# SCH_Amiga-KickSmash-32-in-system-flash_2.net
KiCad netlist of a schematic drawn in EasyEDA
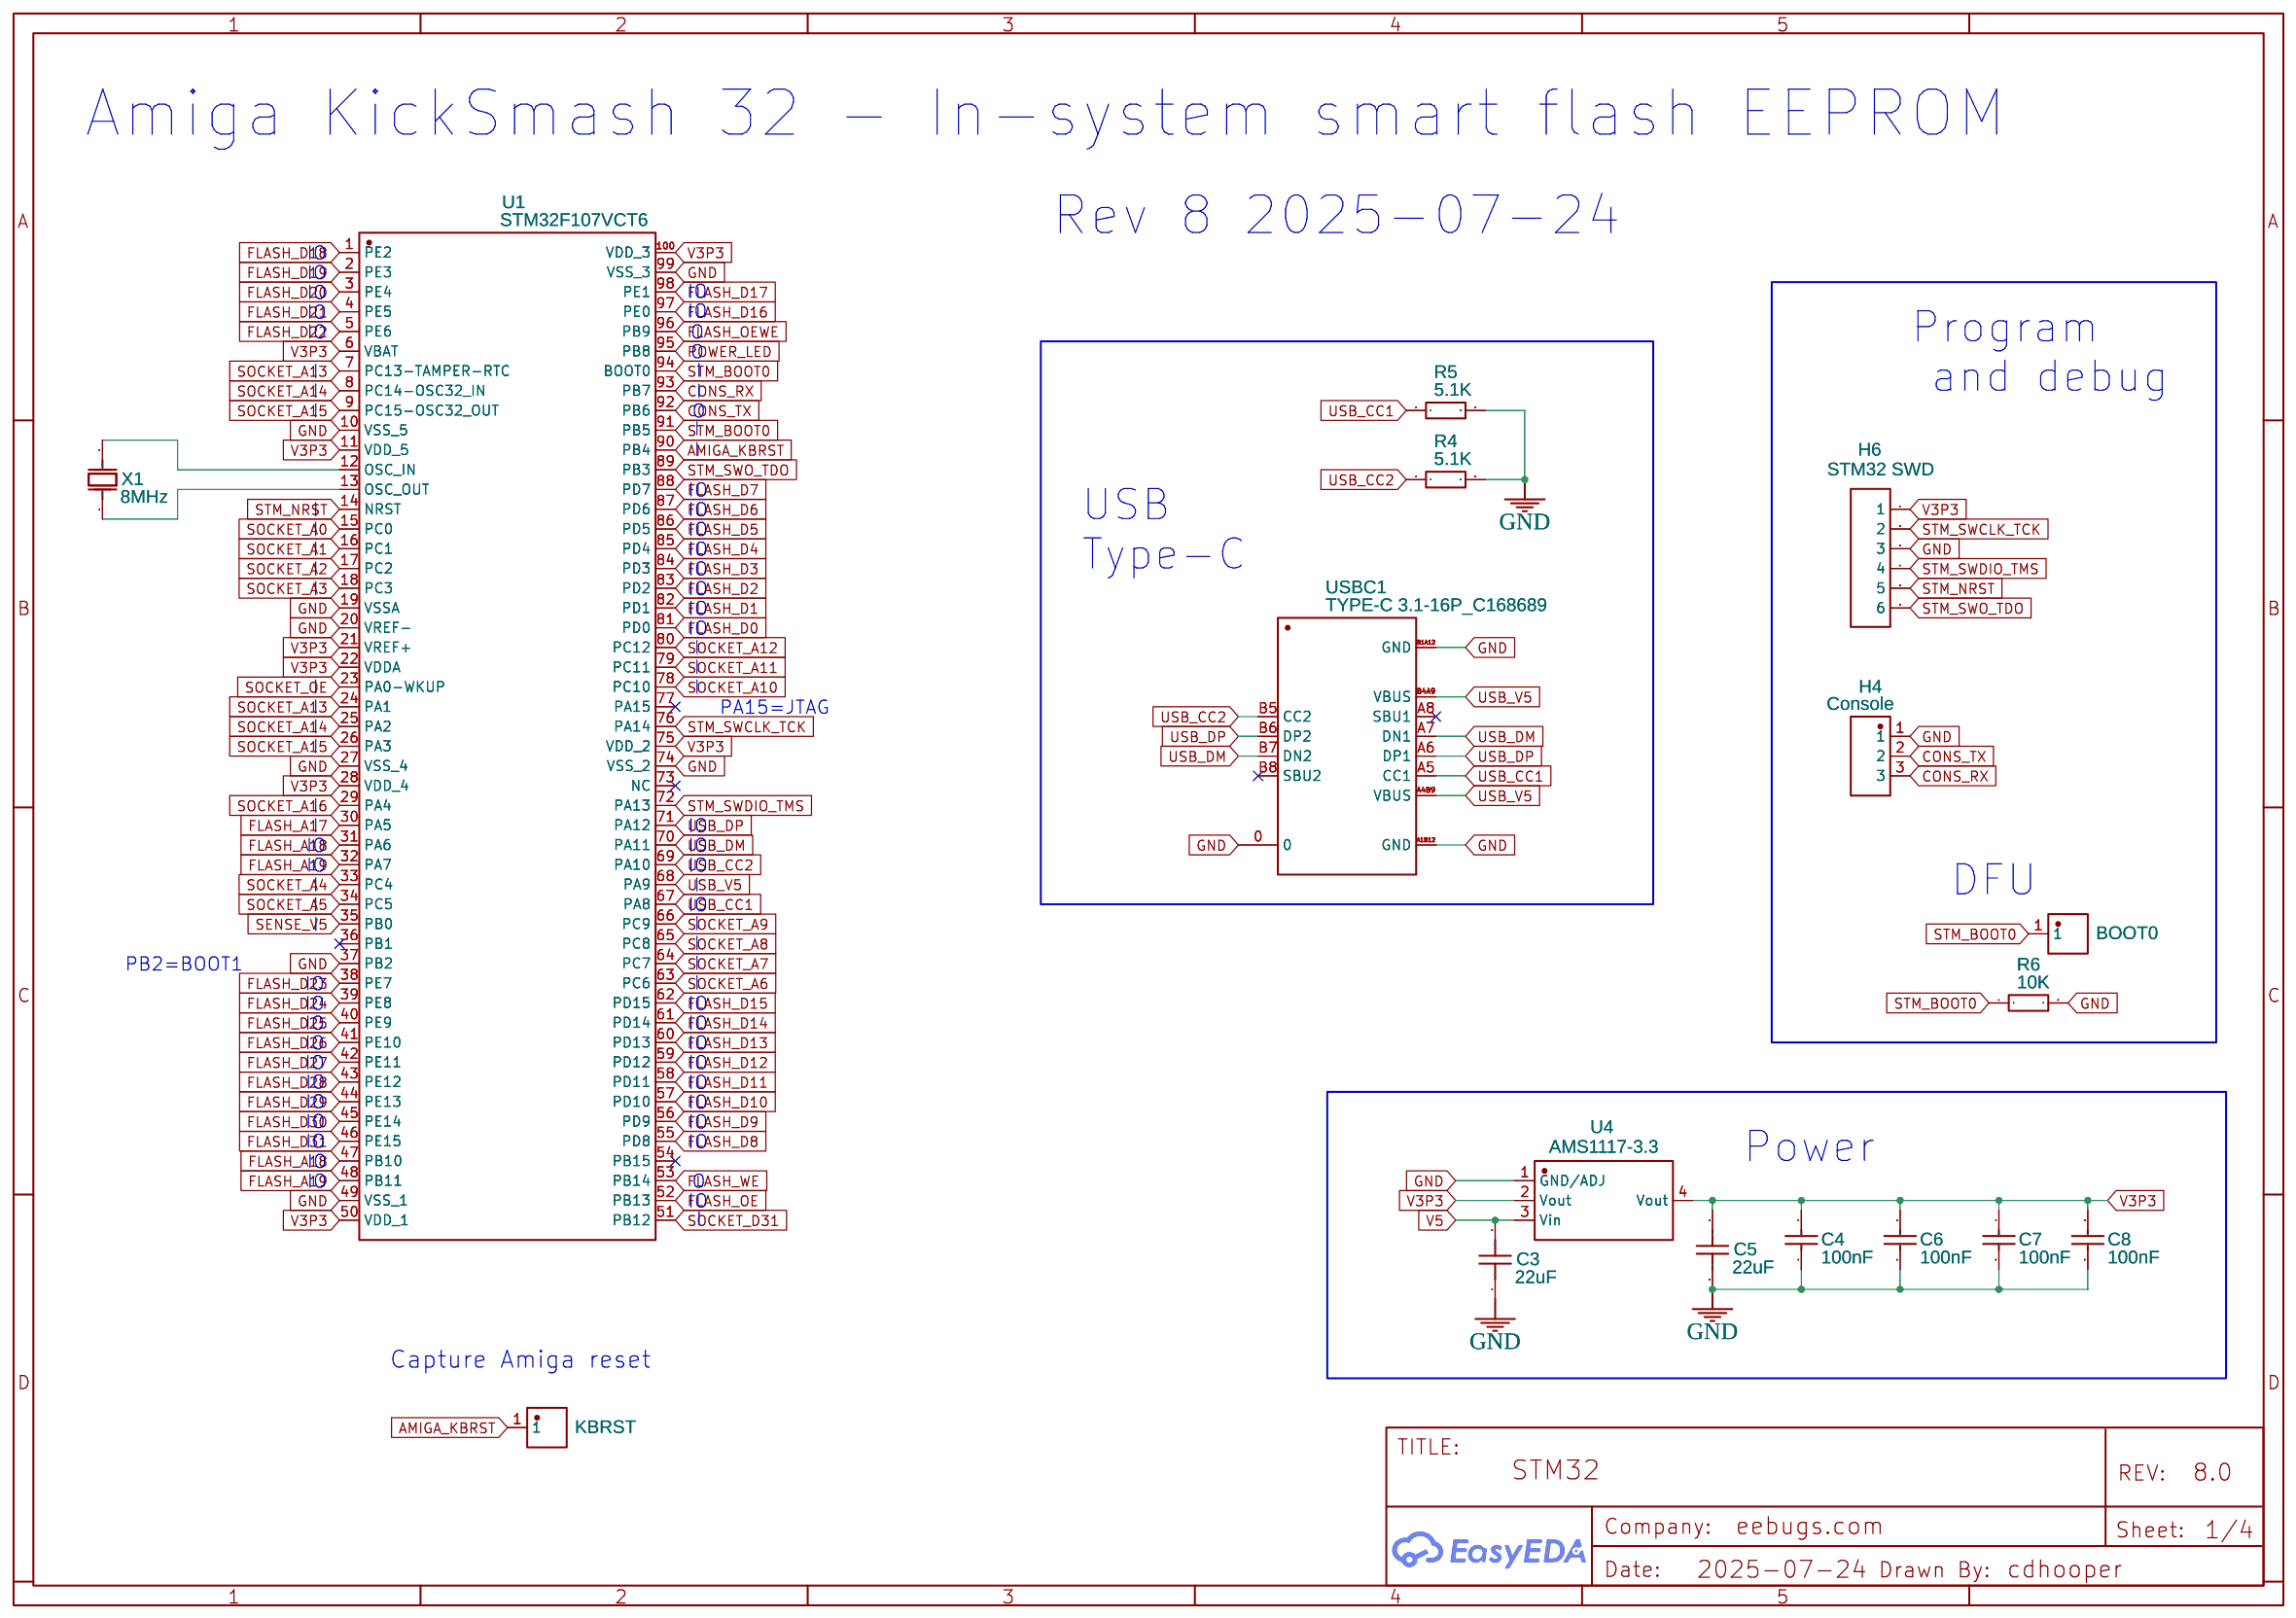
[diagram p0: STM32]
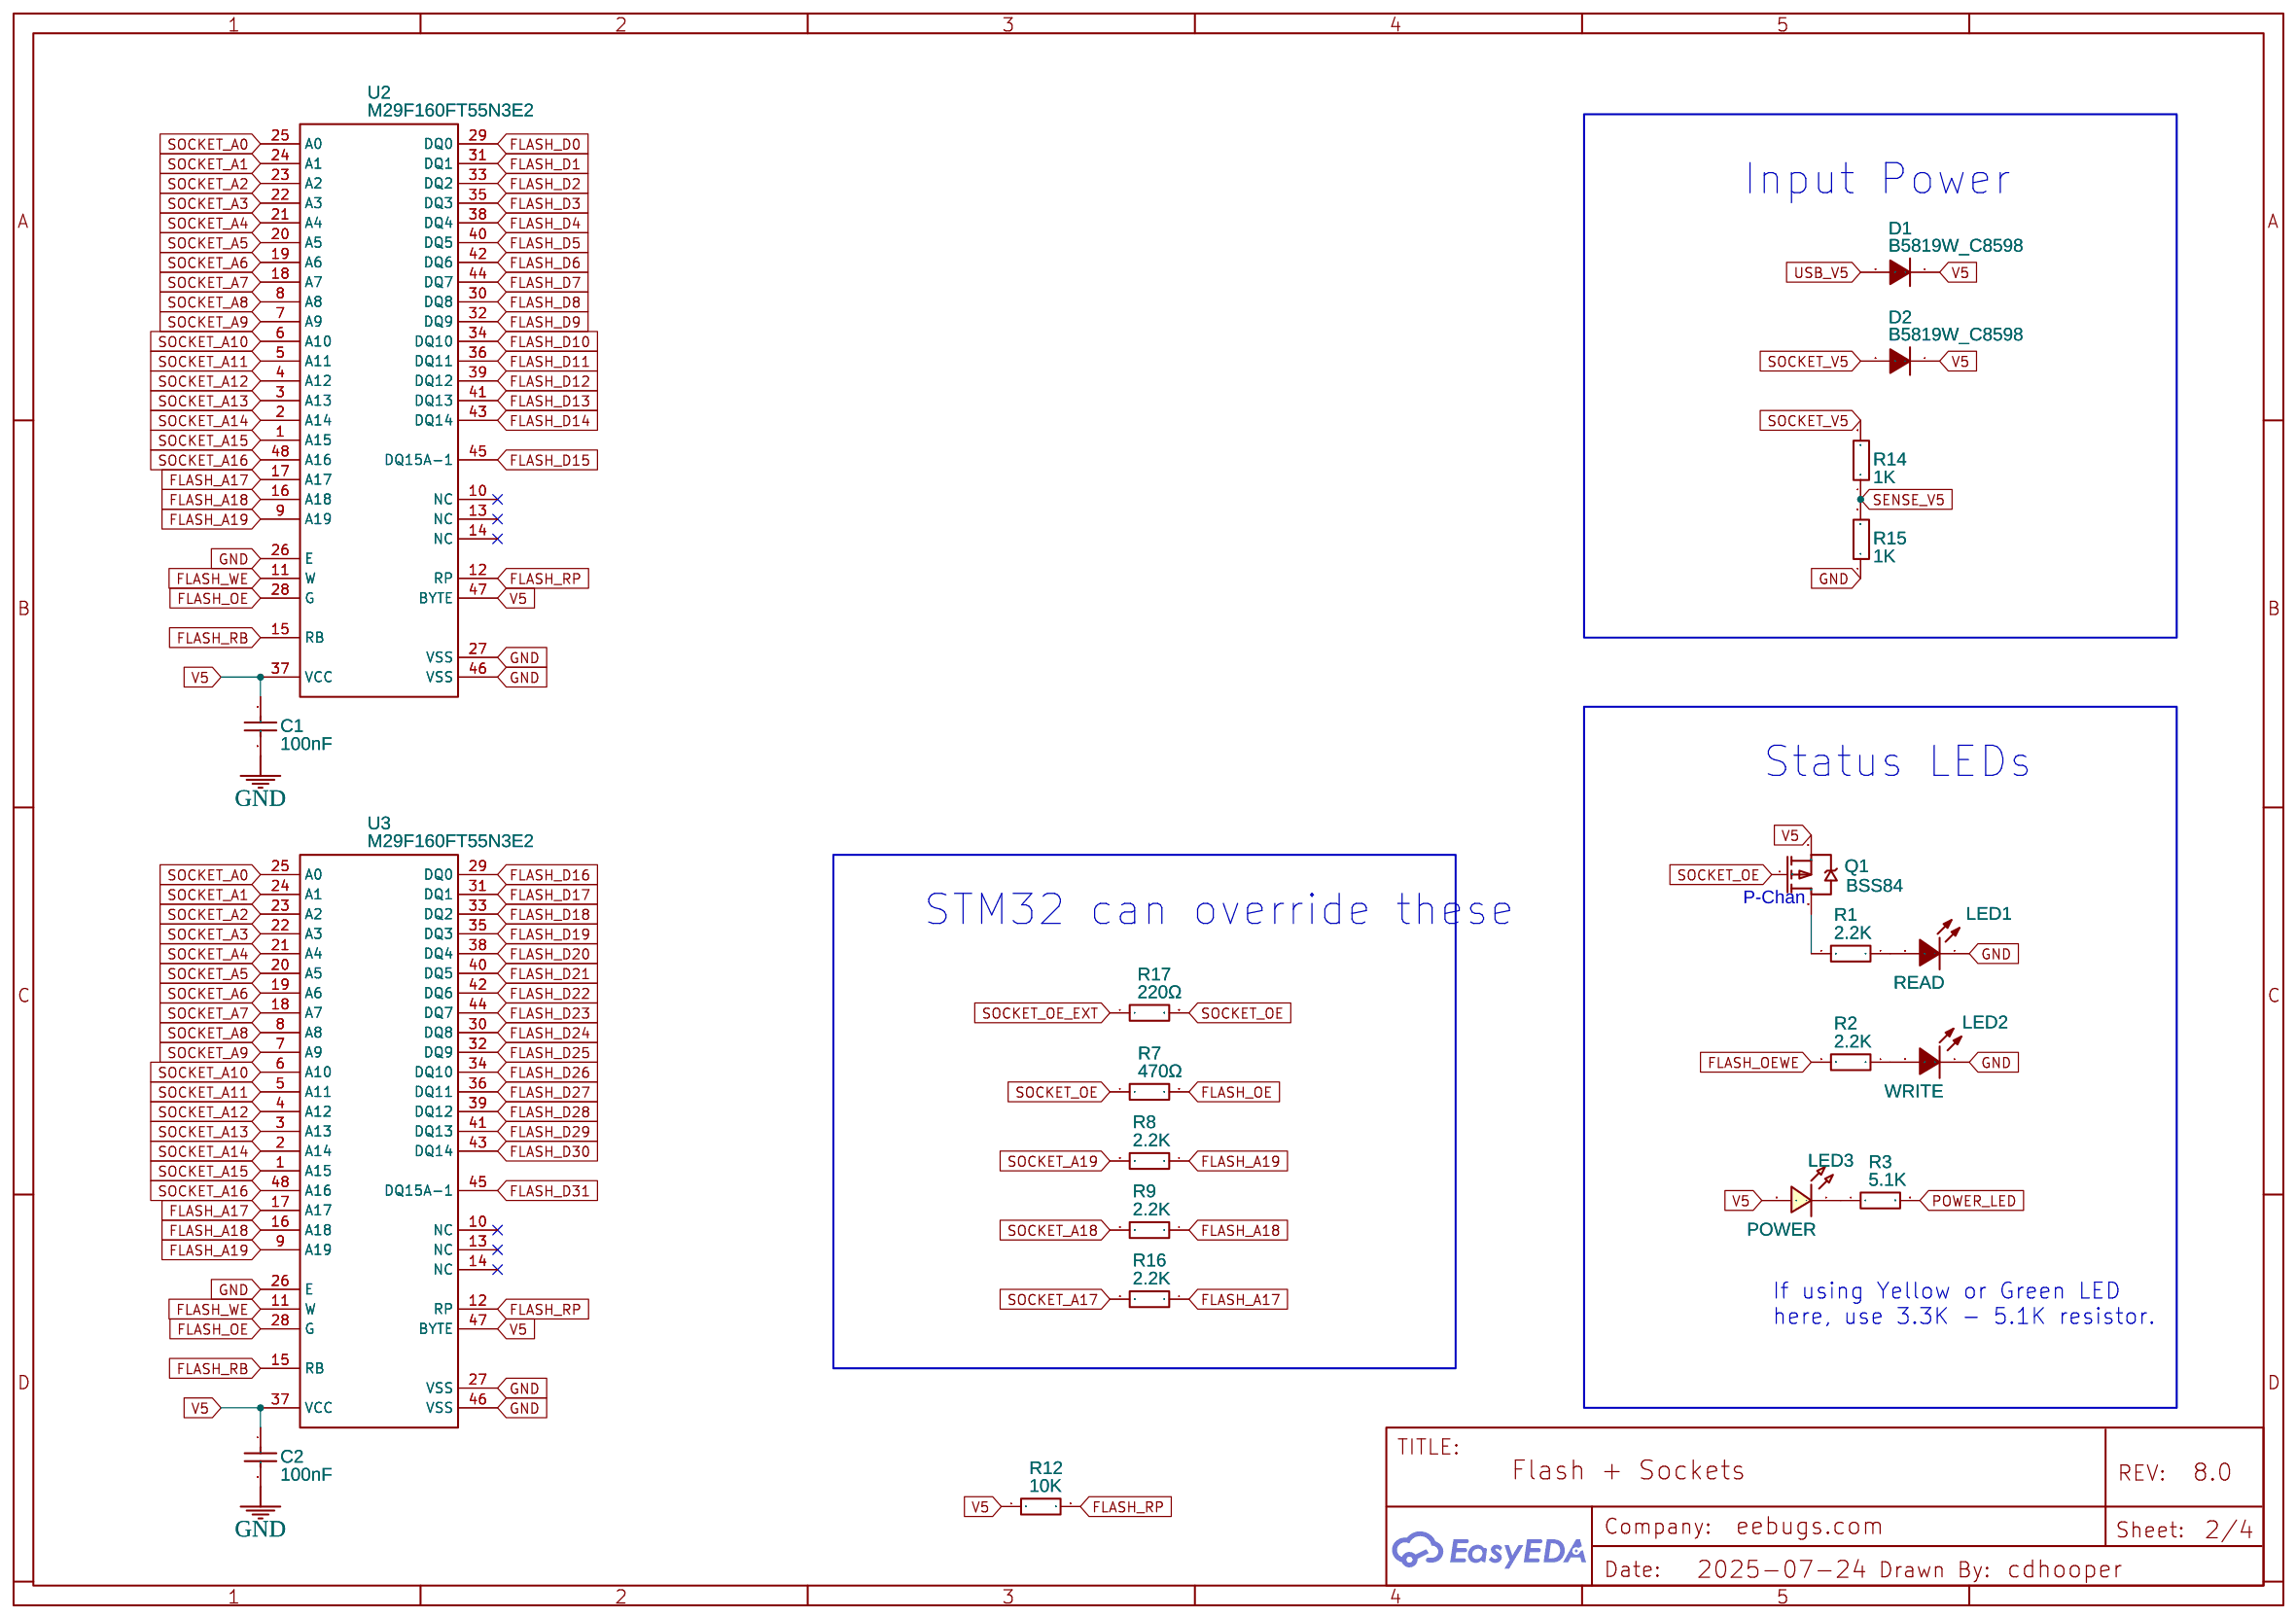
[diagram p1: Flash]
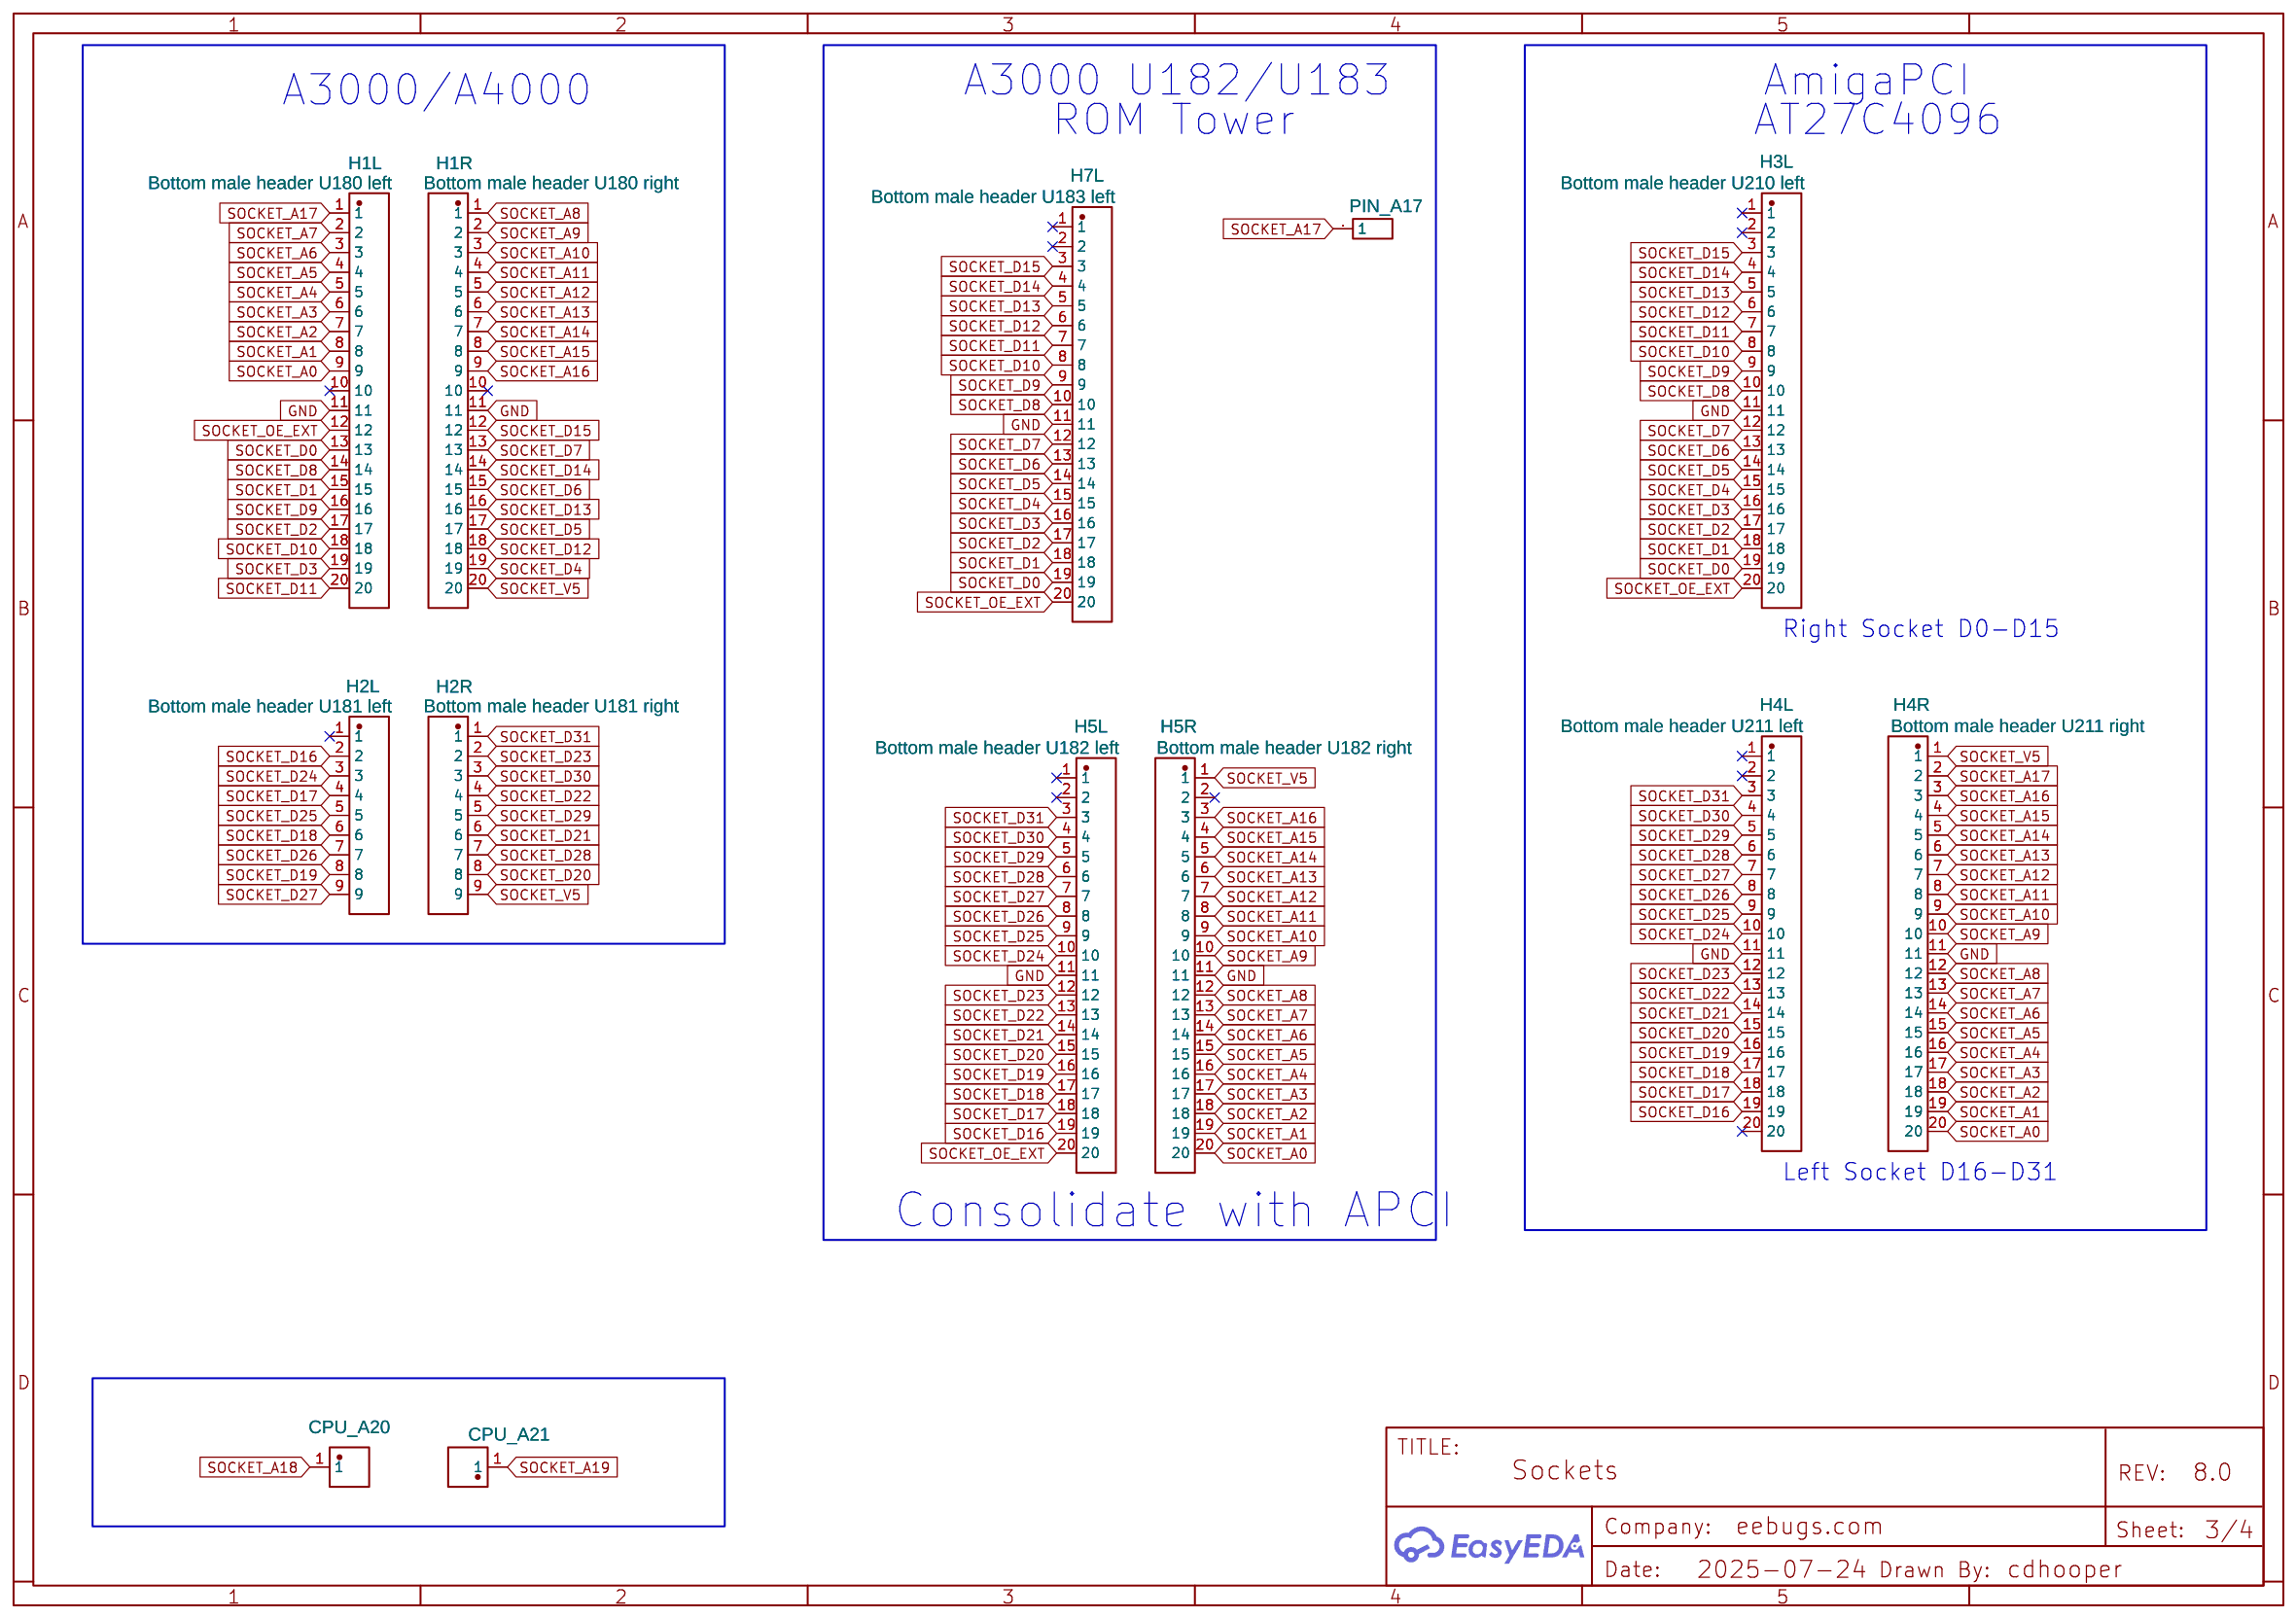
[diagram p2: Sockets]
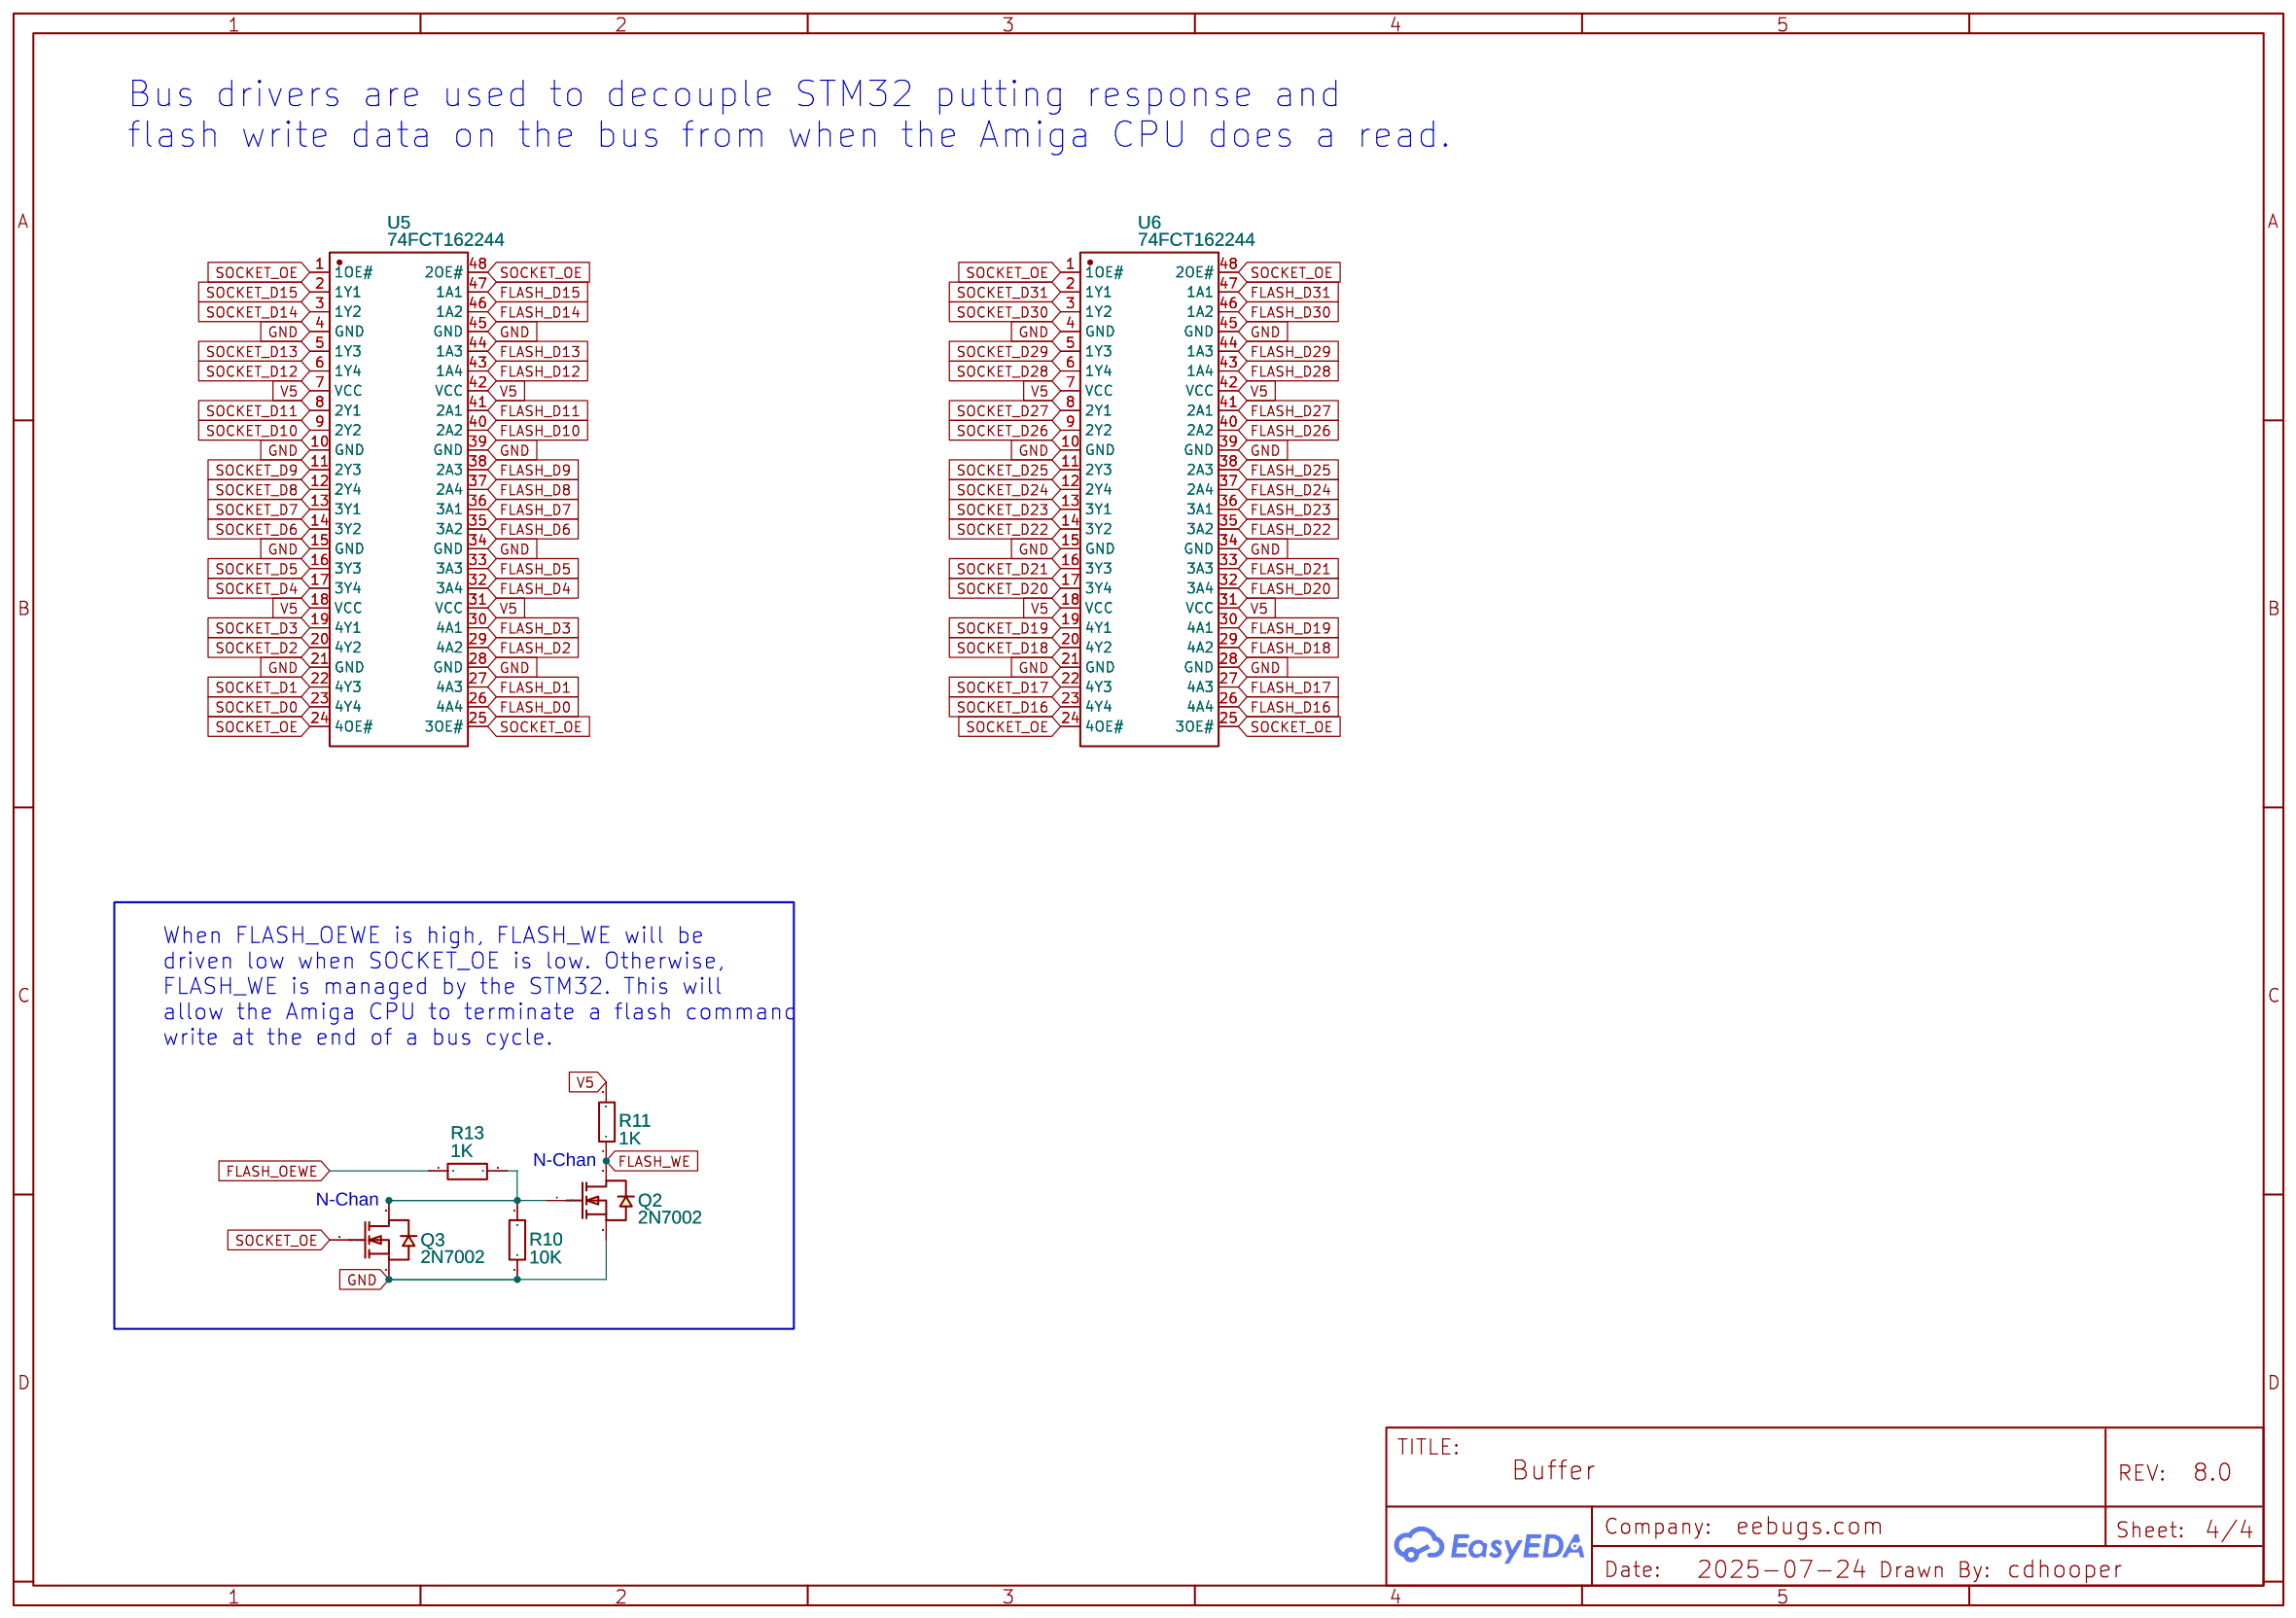
[diagram p3: Buffer]

(export (version "E")
  (design (tool "Eeschema 10.0.6"))
  (components
    (comp (ref "C3")
      (value "22uF")
      (fields (field (name "Manufacturer Part") "CL21A226MAQNNNE") (field (name "Manufacturer") "SAMSUNG"))
      (libsource (lib "") (part "CL21A226MAQNNNE"))
    )
    (comp (ref "C4")
      (value "100nF")
      (fields (field (name "Manufacturer Part") "CC0805KRX7R9BB104") (field (name "Manufacturer") "YAGEO"))
      (libsource (lib "") (part "CC0805KRX7R9BB104"))
    )
    (comp (ref "C5")
      (value "22uF")
      (fields (field (name "Manufacturer Part") "CL21A226MAQNNNE") (field (name "Manufacturer") "SAMSUNG"))
      (libsource (lib "") (part "CL21A226MAQNNNE"))
    )
    (comp (ref "C6")
      (value "100nF")
      (fields (field (name "Manufacturer Part") "CC0805KRX7R9BB104") (field (name "Manufacturer") "YAGEO"))
      (libsource (lib "") (part "CC0805KRX7R9BB104"))
    )
    (comp (ref "C7")
      (value "100nF")
      (fields (field (name "Manufacturer Part") "CC0805KRX7R9BB104") (field (name "Manufacturer") "YAGEO"))
      (libsource (lib "") (part "CC0805KRX7R9BB104"))
    )
    (comp (ref "C8")
      (value "100nF")
      (fields (field (name "Manufacturer Part") "CC0805KRX7R9BB104") (field (name "Manufacturer") "YAGEO"))
      (libsource (lib "") (part "CC0805KRX7R9BB104"))
    )
    (comp (ref "H3")
      (value "KBRST")
      (fields
        (field (name "Manufacturer Part") "X6511WR-01H-C60D30R2")
        (field (name "Manufacturer") "XKB Connection(中国星坤)")
      )
      (libsource (lib "") (part "X6511WR-01H-C30D60R2"))
    )
    (comp (ref "H4")
      (value "Console")
      (fields (field (name "Manufacturer Part") "PZ254R-11-03P") (field (name "Manufacturer") "XFCN(兴飞)"))
      (libsource (lib "") (part "PZ254R-11-03P"))
    )
    (comp (ref "H5")
      (value "BOOT0")
      (fields
        (field (name "Manufacturer Part") "X6511WR-01H-C60D30R2")
        (field (name "Manufacturer") "XKB Connection(中国星坤)")
      )
      (libsource (lib "") (part "X6511WR-01H-C30D60R2"))
    )
    (comp (ref "H6")
      (value "STM32 SWD")
      (fields (field (name "Manufacturer Part") "Female header 1*6p") (field (name "Manufacturer") "BOOMELE"))
      (libsource (lib "") (part "Unknown_945_-530"))
    )
    (comp (ref "R4")
      (value "5.1K")
      (fields (field (name "Manufacturer Part") "0805W8F5101T5E") (field (name "Manufacturer") "UniOhm"))
      (libsource (lib "") (part "0805W8F5101T5E"))
    )
    (comp (ref "R5")
      (value "5.1K")
      (fields (field (name "Manufacturer Part") "0805W8F5101T5E") (field (name "Manufacturer") "UniOhm"))
      (libsource (lib "") (part "0805W8F5101T5E"))
    )
    (comp (ref "R6")
      (value "10K")
      (fields (field (name "Manufacturer Part") "0805W8F1002T5E") (field (name "Manufacturer") "UniOhm"))
      (libsource (lib "") (part "0805W8F1002T5E"))
    )
    (comp (ref "U1")
      (value "STM32F107VCT6")
      (fields (field (name "Manufacturer") "STMicroelectronics"))
      (libsource (lib "") (part "STM32F107VCT6"))
    )
    (comp (ref "U4")
      (value "AMS1117-3.3")
      (fields (field (name "Manufacturer") "AMS"))
      (libsource (lib "") (part "AMS1117-3.3"))
    )
    (comp (ref "USBC1")
      (value "TYPE-C 3.1-16P_C168689")
      (fields (field (name "Manufacturer") "LCSC"))
      (libsource (lib "") (part "TYPE-C 3.1-16P_C168689"))
    )
    (comp (ref "X1")
      (value "8MHz")
      (fields (field (name "Manufacturer Part") "X50328MSB2GI") (field (name "Manufacturer") "YXC"))
      (libsource (lib "") (part "X50328MSB2GI"))
    )
    (comp (ref "C1")
      (value "100nF")
      (fields (field (name "Manufacturer Part") "CC0805KRX7R9BB104") (field (name "Manufacturer") "YAGEO"))
      (libsource (lib "") (part "CC0805KRX7R9BB104"))
    )
    (comp (ref "C2")
      (value "100nF")
      (fields (field (name "Manufacturer Part") "CC0805KRX7R9BB104") (field (name "Manufacturer") "YAGEO"))
      (libsource (lib "") (part "CC0805KRX7R9BB104"))
    )
    (comp (ref "D1")
      (value "B5819W_C8598")
      (fields (field (name "Manufacturer Part") "B5819W") (field (name "Manufacturer") "CJ"))
      (libsource (lib "") (part "B5819W_C8598"))
    )
    (comp (ref "D2")
      (value "B5819W_C8598")
      (fields (field (name "Manufacturer Part") "B5819W") (field (name "Manufacturer") "CJ"))
      (libsource (lib "") (part "B5819W_C8598"))
    )
    (comp (ref "LED1")
      (value "READ")
      (fields (field (name "Manufacturer Part") "17-21SUYC/TR8") (field (name "Manufacturer") "KENTO"))
      (libsource (lib "") (part "17-21SUYC/TR8"))
    )
    (comp (ref "LED2")
      (value "WRITE")
      (fields (field (name "Manufacturer Part") "0805G (Green)") (field (name "Manufacturer") "KENTO"))
      (libsource (lib "") (part "0805G (Green)"))
    )
    (comp (ref "LED3")
      (value "POWER")
      (fields
        (field (name "Manufacturer Part") "P2-0805UVTCS2-0.8T")
        (field (name "Manufacturer") "TUOZHAN(拓展光电)")
      )
      (libsource (lib "") (part "P2-0805UVTCS2-0.8T"))
    )
    (comp (ref "Q1")
      (value "BSS84")
      (fields (field (name "Manufacturer Part") "LBSS84LT1G") (field (name "Manufacturer") "LRC"))
      (libsource (lib "") (part "Unknown_905_-370"))
    )
    (comp (ref "R1")
      (value "2.2K")
      (fields (field (name "Manufacturer Part") "0805W8F2201T5E") (field (name "Manufacturer") "UniOhm"))
      (libsource (lib "") (part "0805W8F2201T5E"))
    )
    (comp (ref "R2")
      (value "2.2K")
      (fields (field (name "Manufacturer Part") "0805W8F2201T5E") (field (name "Manufacturer") "UniOhm"))
      (libsource (lib "") (part "0805W8F2201T5E"))
    )
    (comp (ref "R3")
      (value "5.1K")
      (fields (field (name "Manufacturer Part") "0805W8F5101T5E") (field (name "Manufacturer") "UniOhm"))
      (libsource (lib "") (part "0805W8F5101T5E"))
    )
    (comp (ref "R7")
      (value "470Ω")
      (fields
        (field (name "Manufacturer Part") "0805W8F4700T5E")
        (field (name "Manufacturer") "UNI-ROYAL(厚声)")
      )
      (libsource (lib "") (part "0805W8F4700T5E"))
    )
    (comp (ref "R8")
      (value "2.2K")
      (fields (field (name "Manufacturer Part") "0805W8F2201T5E") (field (name "Manufacturer") "UniOhm"))
      (libsource (lib "") (part "0805W8F2201T5E"))
    )
    (comp (ref "R9")
      (value "2.2K")
      (fields (field (name "Manufacturer Part") "0805W8F2201T5E") (field (name "Manufacturer") "UniOhm"))
      (libsource (lib "") (part "0805W8F2201T5E"))
    )
    (comp (ref "R12")
      (value "10K")
      (fields (field (name "Manufacturer Part") "0805W8F1002T5E") (field (name "Manufacturer") "UniOhm"))
      (libsource (lib "") (part "0805W8F1002T5E"))
    )
    (comp (ref "R14")
      (value "1K")
      (fields (field (name "Manufacturer Part") "0805W8F1001T5E") (field (name "Manufacturer") "UniOhm"))
      (libsource (lib "") (part "0805W8F1001T5E"))
    )
    (comp (ref "R15")
      (value "1K")
      (fields (field (name "Manufacturer Part") "0805W8F1001T5E") (field (name "Manufacturer") "UniOhm"))
      (libsource (lib "") (part "0805W8F1001T5E"))
    )
    (comp (ref "R16")
      (value "2.2K")
      (fields (field (name "Manufacturer Part") "0805W8F2201T5E") (field (name "Manufacturer") "UniOhm"))
      (libsource (lib "") (part "0805W8F2201T5E"))
    )
    (comp (ref "R17")
      (value "220Ω")
      (fields
        (field (name "Manufacturer Part") "0805W8F2200T5E")
        (field (name "Manufacturer") "UNI-ROYAL(厚声)")
      )
      (libsource (lib "") (part "0805W8F2200T5E"))
    )
    (comp (ref "U2") (value "M29F160FT55N3E2") (libsource (lib "") (part "M29F160FT55N3E2")))
    (comp (ref "U3") (value "M29F160FT55N3E2") (libsource (lib "") (part "M29F160FT55N3E2")))
    (comp (ref "H1L")
      (value "Bottom male header U180 left")
      (fields (field (name "Manufacturer Part") "PZ254-1-20-Z-C") (field (name "Manufacturer") "HCTL(华灿天禄)"))
      (libsource (lib "") (part "PZ254-1-20-Z-C_1"))
    )
    (comp (ref "H1R")
      (value "Bottom male header U180 right")
      (fields (field (name "Manufacturer Part") "PZ254-1-20-Z-C") (field (name "Manufacturer") "HCTL(华灿天禄)"))
      (libsource (lib "") (part "PZ254-1-20-Z-C"))
    )
    (comp (ref "H2L")
      (value "Bottom male header U181 left")
      (fields (field (name "Manufacturer Part") "PZ254-1-09-Z-C") (field (name "Manufacturer") "HCTL(华灿天禄)"))
      (libsource (lib "") (part "PZ254-1-09-Z-C_1"))
    )
    (comp (ref "H2R")
      (value "Bottom male header U181 right")
      (fields (field (name "Manufacturer Part") "PZ254-1-09-Z-C") (field (name "Manufacturer") "HCTL(华灿天禄)"))
      (libsource (lib "") (part "PZ254-1-09-Z-C"))
    )
    (comp (ref "H3L")
      (value "Bottom male header U210 left")
      (fields (field (name "Manufacturer Part") "2.54mm 1*20PHeader") (field (name "Manufacturer") "BOOMELE"))
      (libsource (lib "") (part "Header-Male-2.54_1x20_3"))
    )
    (comp (ref "H4L")
      (value "Bottom male header U211 left")
      (fields (field (name "Manufacturer Part") "2.54mm 1*20PHeader") (field (name "Manufacturer") "BOOMELE"))
      (libsource (lib "") (part "Header-Male-2.54_1x20_2"))
    )
    (comp (ref "H4R")
      (value "Bottom male header U211 right")
      (fields (field (name "Manufacturer Part") "2.54mm 1*20PHeader") (field (name "Manufacturer") "BOOMELE"))
      (libsource (lib "") (part "Header-Male-2.54_1x20"))
    )
    (comp (ref "H5L")
      (value "Bottom male header U182 left")
      (fields (field (name "Manufacturer Part") "2.54mm 1*20PHeader") (field (name "Manufacturer") "BOOMELE"))
      (libsource (lib "") (part "Header-Male-2.54_1x20_4"))
    )
    (comp (ref "H5R")
      (value "Bottom male header U182 right")
      (fields (field (name "Manufacturer Part") "2.54mm 1*20PHeader") (field (name "Manufacturer") "BOOMELE"))
      (libsource (lib "") (part "Header-Male-2.54_1x20_5"))
    )
    (comp (ref "H7")
      (value "CPU_A20")
      (fields
        (field (name "Manufacturer Part") "X6511WR-01H-C60D30R2")
        (field (name "Manufacturer") "XKB Connection(中国星坤)")
      )
      (libsource (lib "") (part "X6511WR-01H-C30D60R2_1"))
    )
    (comp (ref "H7L")
      (value "Bottom male header U183 left")
      (fields (field (name "Manufacturer Part") "2.54mm 1*20PHeader") (field (name "Manufacturer") "BOOMELE"))
      (libsource (lib "") (part "Header-Male-2.54_1x20_1"))
    )
    (comp (ref "H8")
      (value "CPU_A21")
      (fields
        (field (name "Manufacturer Part") "X6511WR-01H-C60D30R2")
        (field (name "Manufacturer") "XKB Connection(中国星坤)")
      )
      (libsource (lib "") (part "X6511WR-01H-C30D60R2"))
    )
    (comp (ref "H9")
      (value "PIN_A17")
      (fields
        (field (name "Manufacturer Part") "Header-Male-2.54_1x1")
        (field (name "Manufacturer") "ReliaPro")
      )
      (libsource (lib "") (part "Header-Male-2.54_1x1"))
    )
    (comp (ref "Q2")
      (value "2N7002")
      (fields (field (name "Manufacturer") "CJ(江苏长电/长晶)"))
      (libsource (lib "") (part "AO3400A"))
    )
    (comp (ref "Q3")
      (value "2N7002")
      (fields (field (name "Manufacturer") "CJ(江苏长电/长晶)"))
      (libsource (lib "") (part "AO3400A"))
    )
    (comp (ref "R10")
      (value "10K")
      (fields (field (name "Manufacturer Part") "0805W8F1002T5E") (field (name "Manufacturer") "UniOhm"))
      (libsource (lib "") (part "0805W8F1002T5E"))
    )
    (comp (ref "R11")
      (value "1K")
      (fields (field (name "Manufacturer Part") "0805W8F1001T5E") (field (name "Manufacturer") "UniOhm"))
      (libsource (lib "") (part "0805W8F1001T5E_1"))
    )
    (comp (ref "R13")
      (value "1K")
      (fields (field (name "Manufacturer Part") "0805W8F1001T5E") (field (name "Manufacturer") "UniOhm"))
      (libsource (lib "") (part "0805W8F1001T5E"))
    )
    (comp (ref "U5")
      (value "74FCT162244")
      (fields
        (field (name "Manufacturer Part") "74FCT162244CTPAG")
        (field (name "Manufacturer") "RENESAS(瑞萨)/IDT")
      )
      (libsource (lib "") (part "74FCT162244CTPAG"))
    )
    (comp (ref "U6")
      (value "74FCT162244")
      (fields
        (field (name "Manufacturer Part") "74FCT162244CTPAG")
        (field (name "Manufacturer") "RENESAS(瑞萨)/IDT")
      )
      (libsource (lib "") (part "74FCT162244CTPAG"))
    )
  )
  (nets
    (net (code "1") (name "AMIGA_KBRST") (class "Default")
      (node (ref "H3") (pin "1") (pinfunction "1_1") (pintype "unspecified"))
      (node (ref "U1") (pin "90") (pinfunction "PB4_90") (pintype "unspecified"))
    )
    (net (code "2") (name "CONS_RX") (class "Default")
      (node (ref "H4") (pin "3") (pinfunction "3_3") (pintype "unspecified"))
      (node (ref "U1") (pin "93") (pinfunction "PB7_93") (pintype "unspecified"))
    )
    (net (code "3") (name "CONS_TX") (class "Default")
      (node (ref "H4") (pin "2") (pinfunction "2_2") (pintype "unspecified"))
      (node (ref "U1") (pin "92") (pinfunction "PB6_92") (pintype "unspecified"))
    )
    (net (code "4") (name "FLASH_A17") (class "Default")
      (node (ref "R16") (pin "1") (pinfunction "1_1") (pintype "input"))
      (node (ref "U1") (pin "30") (pinfunction "PA5_30") (pintype "unspecified"))
      (node (ref "U2") (pin "17") (pinfunction "A17_17") (pintype "unspecified"))
      (node (ref "U3") (pin "17") (pinfunction "A17_17") (pintype "unspecified"))
    )
    (net (code "5") (name "FLASH_A18") (class "Default")
      (node (ref "R9") (pin "1") (pinfunction "1_1") (pintype "input"))
      (node (ref "U1") (pin "31") (pinfunction "PA6_31") (pintype "unspecified"))
      (node (ref "U1") (pin "47") (pinfunction "PB10_47") (pintype "unspecified"))
      (node (ref "U2") (pin "16") (pinfunction "A18_16") (pintype "unspecified"))
      (node (ref "U3") (pin "16") (pinfunction "A18_16") (pintype "unspecified"))
    )
    (net (code "6") (name "FLASH_A19") (class "Default")
      (node (ref "R8") (pin "1") (pinfunction "1_1") (pintype "input"))
      (node (ref "U1") (pin "32") (pinfunction "PA7_32") (pintype "unspecified"))
      (node (ref "U1") (pin "48") (pinfunction "PB11_48") (pintype "unspecified"))
      (node (ref "U2") (pin "9") (pinfunction "A19_9") (pintype "unspecified"))
      (node (ref "U3") (pin "9") (pinfunction "A19_9") (pintype "unspecified"))
    )
    (net (code "7") (name "FLASH_D0") (class "Default")
      (node (ref "U1") (pin "81") (pinfunction "PD0_81") (pintype "unspecified"))
      (node (ref "U2") (pin "29") (pinfunction "DQ0_29") (pintype "bidirectional"))
      (node (ref "U5") (pin "26") (pinfunction "4A4_26") (pintype "unspecified"))
    )
    (net (code "8") (name "FLASH_D1") (class "Default")
      (node (ref "U1") (pin "82") (pinfunction "PD1_82") (pintype "unspecified"))
      (node (ref "U2") (pin "31") (pinfunction "DQ1_31") (pintype "bidirectional"))
      (node (ref "U5") (pin "27") (pinfunction "4A3_27") (pintype "unspecified"))
    )
    (net (code "9") (name "FLASH_D2") (class "Default")
      (node (ref "U1") (pin "83") (pinfunction "PD2_83") (pintype "unspecified"))
      (node (ref "U2") (pin "33") (pinfunction "DQ2_33") (pintype "bidirectional"))
      (node (ref "U5") (pin "29") (pinfunction "4A2_29") (pintype "unspecified"))
    )
    (net (code "10") (name "FLASH_D3") (class "Default")
      (node (ref "U1") (pin "84") (pinfunction "PD3_84") (pintype "unspecified"))
      (node (ref "U2") (pin "35") (pinfunction "DQ3_35") (pintype "bidirectional"))
      (node (ref "U5") (pin "30") (pinfunction "4A1_30") (pintype "unspecified"))
    )
    (net (code "11") (name "FLASH_D4") (class "Default")
      (node (ref "U1") (pin "85") (pinfunction "PD4_85") (pintype "unspecified"))
      (node (ref "U2") (pin "38") (pinfunction "DQ4_38") (pintype "bidirectional"))
      (node (ref "U5") (pin "32") (pinfunction "3A4_32") (pintype "unspecified"))
    )
    (net (code "12") (name "FLASH_D5") (class "Default")
      (node (ref "U1") (pin "86") (pinfunction "PD5_86") (pintype "unspecified"))
      (node (ref "U2") (pin "40") (pinfunction "DQ5_40") (pintype "bidirectional"))
      (node (ref "U5") (pin "33") (pinfunction "3A3_33") (pintype "unspecified"))
    )
    (net (code "13") (name "FLASH_D6") (class "Default")
      (node (ref "U1") (pin "87") (pinfunction "PD6_87") (pintype "unspecified"))
      (node (ref "U2") (pin "42") (pinfunction "DQ6_42") (pintype "bidirectional"))
      (node (ref "U5") (pin "35") (pinfunction "3A2_35") (pintype "unspecified"))
    )
    (net (code "14") (name "FLASH_D7") (class "Default")
      (node (ref "U1") (pin "88") (pinfunction "PD7_88") (pintype "unspecified"))
      (node (ref "U2") (pin "44") (pinfunction "DQ7_44") (pintype "bidirectional"))
      (node (ref "U5") (pin "36") (pinfunction "3A1_36") (pintype "unspecified"))
    )
    (net (code "15") (name "FLASH_D8") (class "Default")
      (node (ref "U1") (pin "55") (pinfunction "PD8_55") (pintype "unspecified"))
      (node (ref "U2") (pin "30") (pinfunction "DQ8_30") (pintype "bidirectional"))
      (node (ref "U5") (pin "37") (pinfunction "2A4_37") (pintype "unspecified"))
    )
    (net (code "16") (name "FLASH_D9") (class "Default")
      (node (ref "U1") (pin "56") (pinfunction "PD9_56") (pintype "unspecified"))
      (node (ref "U2") (pin "32") (pinfunction "DQ9_32") (pintype "bidirectional"))
      (node (ref "U5") (pin "38") (pinfunction "2A3_38") (pintype "unspecified"))
    )
    (net (code "17") (name "FLASH_D10") (class "Default")
      (node (ref "U1") (pin "57") (pinfunction "PD10_57") (pintype "unspecified"))
      (node (ref "U2") (pin "34") (pinfunction "DQ10_34") (pintype "bidirectional"))
      (node (ref "U5") (pin "40") (pinfunction "2A2_40") (pintype "unspecified"))
    )
    (net (code "18") (name "FLASH_D11") (class "Default")
      (node (ref "U1") (pin "58") (pinfunction "PD11_58") (pintype "unspecified"))
      (node (ref "U2") (pin "36") (pinfunction "DQ11_36") (pintype "bidirectional"))
      (node (ref "U5") (pin "41") (pinfunction "2A1_41") (pintype "unspecified"))
    )
    (net (code "19") (name "FLASH_D12") (class "Default")
      (node (ref "U1") (pin "59") (pinfunction "PD12_59") (pintype "unspecified"))
      (node (ref "U2") (pin "39") (pinfunction "DQ12_39") (pintype "bidirectional"))
      (node (ref "U5") (pin "43") (pinfunction "1A4_43") (pintype "unspecified"))
    )
    (net (code "20") (name "FLASH_D13") (class "Default")
      (node (ref "U1") (pin "60") (pinfunction "PD13_60") (pintype "unspecified"))
      (node (ref "U2") (pin "41") (pinfunction "DQ13_41") (pintype "bidirectional"))
      (node (ref "U5") (pin "44") (pinfunction "1A3_44") (pintype "unspecified"))
    )
    (net (code "21") (name "FLASH_D14") (class "Default")
      (node (ref "U1") (pin "61") (pinfunction "PD14_61") (pintype "unspecified"))
      (node (ref "U2") (pin "43") (pinfunction "DQ14_43") (pintype "bidirectional"))
      (node (ref "U5") (pin "46") (pinfunction "1A2_46") (pintype "unspecified"))
    )
    (net (code "22") (name "FLASH_D15") (class "Default")
      (node (ref "U1") (pin "62") (pinfunction "PD15_62") (pintype "unspecified"))
      (node (ref "U2") (pin "45") (pinfunction "DQ15A-1_45") (pintype "bidirectional"))
      (node (ref "U5") (pin "47") (pinfunction "1A1_47") (pintype "unspecified"))
    )
    (net (code "23") (name "FLASH_D16") (class "Default")
      (node (ref "U1") (pin "97") (pinfunction "PE0_97") (pintype "unspecified"))
      (node (ref "U3") (pin "29") (pinfunction "DQ0_29") (pintype "bidirectional"))
      (node (ref "U6") (pin "26") (pinfunction "4A4_26") (pintype "unspecified"))
    )
    (net (code "24") (name "FLASH_D17") (class "Default")
      (node (ref "U1") (pin "98") (pinfunction "PE1_98") (pintype "unspecified"))
      (node (ref "U3") (pin "31") (pinfunction "DQ1_31") (pintype "bidirectional"))
      (node (ref "U6") (pin "27") (pinfunction "4A3_27") (pintype "unspecified"))
    )
    (net (code "25") (name "FLASH_D18") (class "Default")
      (node (ref "U1") (pin "1") (pinfunction "PE2_1") (pintype "unspecified"))
      (node (ref "U3") (pin "33") (pinfunction "DQ2_33") (pintype "bidirectional"))
      (node (ref "U6") (pin "29") (pinfunction "4A2_29") (pintype "unspecified"))
    )
    (net (code "26") (name "FLASH_D19") (class "Default")
      (node (ref "U1") (pin "2") (pinfunction "PE3_2") (pintype "unspecified"))
      (node (ref "U3") (pin "35") (pinfunction "DQ3_35") (pintype "bidirectional"))
      (node (ref "U6") (pin "30") (pinfunction "4A1_30") (pintype "unspecified"))
    )
    (net (code "27") (name "FLASH_D20") (class "Default")
      (node (ref "U1") (pin "3") (pinfunction "PE4_3") (pintype "unspecified"))
      (node (ref "U3") (pin "38") (pinfunction "DQ4_38") (pintype "bidirectional"))
      (node (ref "U6") (pin "32") (pinfunction "3A4_32") (pintype "unspecified"))
    )
    (net (code "28") (name "FLASH_D21") (class "Default")
      (node (ref "U1") (pin "4") (pinfunction "PE5_4") (pintype "unspecified"))
      (node (ref "U3") (pin "40") (pinfunction "DQ5_40") (pintype "bidirectional"))
      (node (ref "U6") (pin "33") (pinfunction "3A3_33") (pintype "unspecified"))
    )
    (net (code "29") (name "FLASH_D22") (class "Default")
      (node (ref "U1") (pin "5") (pinfunction "PE6_5") (pintype "unspecified"))
      (node (ref "U3") (pin "42") (pinfunction "DQ6_42") (pintype "bidirectional"))
      (node (ref "U6") (pin "35") (pinfunction "3A2_35") (pintype "unspecified"))
    )
    (net (code "30") (name "FLASH_D23") (class "Default")
      (node (ref "U1") (pin "38") (pinfunction "PE7_38") (pintype "unspecified"))
      (node (ref "U3") (pin "44") (pinfunction "DQ7_44") (pintype "bidirectional"))
      (node (ref "U6") (pin "36") (pinfunction "3A1_36") (pintype "unspecified"))
    )
    (net (code "31") (name "FLASH_D24") (class "Default")
      (node (ref "U1") (pin "39") (pinfunction "PE8_39") (pintype "unspecified"))
      (node (ref "U3") (pin "30") (pinfunction "DQ8_30") (pintype "bidirectional"))
      (node (ref "U6") (pin "37") (pinfunction "2A4_37") (pintype "unspecified"))
    )
    (net (code "32") (name "FLASH_D25") (class "Default")
      (node (ref "U1") (pin "40") (pinfunction "PE9_40") (pintype "unspecified"))
      (node (ref "U3") (pin "32") (pinfunction "DQ9_32") (pintype "bidirectional"))
      (node (ref "U6") (pin "38") (pinfunction "2A3_38") (pintype "unspecified"))
    )
    (net (code "33") (name "FLASH_D26") (class "Default")
      (node (ref "U1") (pin "41") (pinfunction "PE10_41") (pintype "unspecified"))
      (node (ref "U3") (pin "34") (pinfunction "DQ10_34") (pintype "bidirectional"))
      (node (ref "U6") (pin "40") (pinfunction "2A2_40") (pintype "unspecified"))
    )
    (net (code "34") (name "FLASH_D27") (class "Default")
      (node (ref "U1") (pin "42") (pinfunction "PE11_42") (pintype "unspecified"))
      (node (ref "U3") (pin "36") (pinfunction "DQ11_36") (pintype "bidirectional"))
      (node (ref "U6") (pin "41") (pinfunction "2A1_41") (pintype "unspecified"))
    )
    (net (code "35") (name "FLASH_D28") (class "Default")
      (node (ref "U1") (pin "43") (pinfunction "PE12_43") (pintype "unspecified"))
      (node (ref "U3") (pin "39") (pinfunction "DQ12_39") (pintype "bidirectional"))
      (node (ref "U6") (pin "43") (pinfunction "1A4_43") (pintype "unspecified"))
    )
    (net (code "36") (name "FLASH_D29") (class "Default")
      (node (ref "U1") (pin "44") (pinfunction "PE13_44") (pintype "unspecified"))
      (node (ref "U3") (pin "41") (pinfunction "DQ13_41") (pintype "bidirectional"))
      (node (ref "U6") (pin "44") (pinfunction "1A3_44") (pintype "unspecified"))
    )
    (net (code "37") (name "FLASH_D30") (class "Default")
      (node (ref "U1") (pin "45") (pinfunction "PE14_45") (pintype "unspecified"))
      (node (ref "U3") (pin "43") (pinfunction "DQ14_43") (pintype "bidirectional"))
      (node (ref "U6") (pin "46") (pinfunction "1A2_46") (pintype "unspecified"))
    )
    (net (code "38") (name "FLASH_D31") (class "Default")
      (node (ref "U1") (pin "46") (pinfunction "PE15_46") (pintype "unspecified"))
      (node (ref "U3") (pin "45") (pinfunction "DQ15A-1_45") (pintype "bidirectional"))
      (node (ref "U6") (pin "47") (pinfunction "1A1_47") (pintype "unspecified"))
    )
    (net (code "39") (name "FLASH_OE") (class "Default")
      (node (ref "R7") (pin "2") (pinfunction "2_2") (pintype "input"))
      (node (ref "U1") (pin "52") (pinfunction "PB13_52") (pintype "unspecified"))
      (node (ref "U2") (pin "28") (pinfunction "G_28") (pintype "unspecified"))
      (node (ref "U3") (pin "28") (pinfunction "G_28") (pintype "unspecified"))
    )
    (net (code "40") (name "FLASH_OEWE") (class "Default")
      (node (ref "R13") (pin "1") (pinfunction "1_1") (pintype "input"))
      (node (ref "R2") (pin "2") (pinfunction "2_2") (pintype "input"))
      (node (ref "U1") (pin "96") (pinfunction "PB9_96") (pintype "unspecified"))
    )
    (net (code "41") (name "FLASH_RB") (class "Default")
      (node (ref "U2") (pin "15") (pinfunction "RB_15") (pintype "unspecified"))
      (node (ref "U3") (pin "15") (pinfunction "RB_15") (pintype "unspecified"))
    )
    (net (code "42") (name "FLASH_RP") (class "Default")
      (node (ref "R12") (pin "2") (pinfunction "2_2") (pintype "input"))
      (node (ref "U2") (pin "12") (pinfunction "RP_12") (pintype "unspecified"))
      (node (ref "U3") (pin "12") (pinfunction "RP_12") (pintype "unspecified"))
    )
    (net (code "43") (name "FLASH_WE") (class "Default")
      (node (ref "Q2") (pin "3") (pinfunction "D_3") (pintype "unspecified"))
      (node (ref "R11") (pin "1") (pinfunction "1_1") (pintype "input"))
      (node (ref "U1") (pin "53") (pinfunction "PB14_53") (pintype "unspecified"))
      (node (ref "U2") (pin "11") (pinfunction "W_11") (pintype "unspecified"))
      (node (ref "U3") (pin "11") (pinfunction "W_11") (pintype "unspecified"))
    )
    (net (code "44") (name "GND") (class "Default")
      (node (ref "C1") (pin "2") (pinfunction "2_2") (pintype "input"))
      (node (ref "C2") (pin "2") (pinfunction "2_2") (pintype "input"))
      (node (ref "C3") (pin "1") (pinfunction "1_1") (pintype "unspecified"))
      (node (ref "C4") (pin "2") (pinfunction "2_2") (pintype "input"))
      (node (ref "C5") (pin "1") (pinfunction "1_1") (pintype "unspecified"))
      (node (ref "C6") (pin "2") (pinfunction "2_2") (pintype "input"))
      (node (ref "C7") (pin "2") (pinfunction "2_2") (pintype "input"))
      (node (ref "C8") (pin "2") (pinfunction "2_2") (pintype "input"))
      (node (ref "H1L") (pin "11") (pinfunction "11_11") (pintype "unspecified"))
      (node (ref "H1R") (pin "11") (pinfunction "11_11") (pintype "unspecified"))
      (node (ref "H3L") (pin "11") (pinfunction "11_11") (pintype "unspecified"))
      (node (ref "H4") (pin "1") (pinfunction "1_1") (pintype "unspecified"))
      (node (ref "H4L") (pin "11") (pinfunction "11_11") (pintype "unspecified"))
      (node (ref "H4R") (pin "11") (pinfunction "11_11") (pintype "unspecified"))
      (node (ref "H5L") (pin "11") (pinfunction "11_11") (pintype "unspecified"))
      (node (ref "H5R") (pin "11") (pinfunction "11_11") (pintype "unspecified"))
      (node (ref "H6") (pin "3") (pinfunction "3_3") (pintype "input"))
      (node (ref "H7L") (pin "11") (pinfunction "11_11") (pintype "unspecified"))
      (node (ref "LED1") (pin "1") (pinfunction "-_1") (pintype "unspecified"))
      (node (ref "LED2") (pin "1") (pinfunction "K_1") (pintype "unspecified"))
      (node (ref "Q2") (pin "2") (pinfunction "S_2") (pintype "unspecified"))
      (node (ref "Q3") (pin "2") (pinfunction "S_2") (pintype "unspecified"))
      (node (ref "R10") (pin "2") (pinfunction "2_2") (pintype "input"))
      (node (ref "R15") (pin "1") (pinfunction "1_1") (pintype "input"))
      (node (ref "R4") (pin "2") (pinfunction "2_2") (pintype "input"))
      (node (ref "R5") (pin "2") (pinfunction "2_2") (pintype "input"))
      (node (ref "R6") (pin "2") (pinfunction "2_2") (pintype "input"))
      (node (ref "U1") (pin "10") (pinfunction "VSS_5_10") (pintype "unspecified"))
      (node (ref "U1") (pin "19") (pinfunction "VSSA_19") (pintype "unspecified"))
      (node (ref "U1") (pin "20") (pinfunction "VREF-_20") (pintype "unspecified"))
      (node (ref "U1") (pin "27") (pinfunction "VSS_4_27") (pintype "unspecified"))
      (node (ref "U1") (pin "37") (pinfunction "PB2_37") (pintype "unspecified"))
      (node (ref "U1") (pin "49") (pinfunction "VSS_1_49") (pintype "unspecified"))
      (node (ref "U1") (pin "74") (pinfunction "VSS_2_74") (pintype "unspecified"))
      (node (ref "U1") (pin "99") (pinfunction "VSS_3_99") (pintype "unspecified"))
      (node (ref "U2") (pin "26") (pinfunction "E_26") (pintype "unspecified"))
      (node (ref "U2") (pin "27") (pinfunction "VSS_27") (pintype "passive"))
      (node (ref "U2") (pin "46") (pinfunction "VSS_46") (pintype "passive"))
      (node (ref "U3") (pin "26") (pinfunction "E_26") (pintype "unspecified"))
      (node (ref "U3") (pin "27") (pinfunction "VSS_27") (pintype "passive"))
      (node (ref "U3") (pin "46") (pinfunction "VSS_46") (pintype "passive"))
      (node (ref "U4") (pin "1") (pinfunction "GND/ADJ_1") (pintype "unspecified"))
      (node (ref "U5") (pin "10") (pinfunction "GND_10") (pintype "unspecified"))
      (node (ref "U5") (pin "15") (pinfunction "GND_15") (pintype "unspecified"))
      (node (ref "U5") (pin "21") (pinfunction "GND_21") (pintype "unspecified"))
      (node (ref "U5") (pin "28") (pinfunction "GND_28") (pintype "unspecified"))
      (node (ref "U5") (pin "34") (pinfunction "GND_34") (pintype "unspecified"))
      (node (ref "U5") (pin "39") (pinfunction "GND_39") (pintype "unspecified"))
      (node (ref "U5") (pin "4") (pinfunction "GND_4") (pintype "unspecified"))
      (node (ref "U5") (pin "45") (pinfunction "GND_45") (pintype "unspecified"))
      (node (ref "U6") (pin "10") (pinfunction "GND_10") (pintype "unspecified"))
      (node (ref "U6") (pin "15") (pinfunction "GND_15") (pintype "unspecified"))
      (node (ref "U6") (pin "21") (pinfunction "GND_21") (pintype "unspecified"))
      (node (ref "U6") (pin "28") (pinfunction "GND_28") (pintype "unspecified"))
      (node (ref "U6") (pin "34") (pinfunction "GND_34") (pintype "unspecified"))
      (node (ref "U6") (pin "39") (pinfunction "GND_39") (pintype "unspecified"))
      (node (ref "U6") (pin "4") (pinfunction "GND_4") (pintype "unspecified"))
      (node (ref "U6") (pin "45") (pinfunction "GND_45") (pintype "unspecified"))
      (node (ref "USBC1") (pin "0") (pinfunction "0_0") (pintype "unspecified"))
      (node (ref "USBC1") (pin "A1B12") (pinfunction "GND_A1B12") (pintype "unspecified"))
      (node (ref "USBC1") (pin "B1A12") (pinfunction "GND_B1A12") (pintype "unspecified"))
    )
    (net (code "45") (name "Net-(LED1-+)") (class "Default")
      (node (ref "LED1") (pin "2") (pinfunction "+_2") (pintype "unspecified"))
      (node (ref "R1") (pin "1") (pinfunction "1_1") (pintype "input"))
    )
    (net (code "46") (name "Net-(LED2-A)") (class "Default")
      (node (ref "LED2") (pin "2") (pinfunction "A_2") (pintype "unspecified"))
      (node (ref "R2") (pin "1") (pinfunction "1_1") (pintype "input"))
    )
    (net (code "47") (name "Net-(LED3--)") (class "Default")
      (node (ref "LED3") (pin "1") (pinfunction "-_1") (pintype "unspecified"))
      (node (ref "R3") (pin "1") (pinfunction "1_1") (pintype "input"))
    )
    (net (code "48") (name "Net-(Q1-D)") (class "Default")
      (node (ref "Q1") (pin "3") (pinfunction "D_3") (pintype "unspecified"))
      (node (ref "R1") (pin "2") (pinfunction "2_2") (pintype "input"))
    )
    (net (code "49") (name "Net-(Q2-G)") (class "Default")
      (node (ref "Q2") (pin "1") (pinfunction "G_1") (pintype "unspecified"))
      (node (ref "Q3") (pin "3") (pinfunction "D_3") (pintype "unspecified"))
      (node (ref "R10") (pin "1") (pinfunction "1_1") (pintype "input"))
      (node (ref "R13") (pin "2") (pinfunction "2_2") (pintype "input"))
    )
    (net (code "50") (name "Net-(U1-OSC_IN)") (class "Default")
      (node (ref "U1") (pin "12") (pinfunction "OSC_IN_12") (pintype "unspecified"))
      (node (ref "X1") (pin "2") (pinfunction "OSC2_2") (pintype "input"))
    )
    (net (code "51") (name "Net-(U1-OSC_OUT)") (class "Default")
      (node (ref "U1") (pin "13") (pinfunction "OSC_OUT_13") (pintype "unspecified"))
      (node (ref "X1") (pin "1") (pinfunction "OSC1_1") (pintype "input"))
    )
    (net (code "52") (name "POWER_LED") (class "Default")
      (node (ref "R3") (pin "2") (pinfunction "2_2") (pintype "input"))
      (node (ref "U1") (pin "95") (pinfunction "PB8_95") (pintype "unspecified"))
    )
    (net (code "53") (name "SENSE_V5") (class "Default")
      (node (ref "R14") (pin "1") (pinfunction "1_1") (pintype "input"))
      (node (ref "R15") (pin "2") (pinfunction "2_2") (pintype "input"))
      (node (ref "U1") (pin "35") (pinfunction "PB0_35") (pintype "unspecified"))
    )
    (net (code "54") (name "SOCKET_A0") (class "Default")
      (node (ref "H1L") (pin "9") (pinfunction "9_9") (pintype "unspecified"))
      (node (ref "H4R") (pin "20") (pinfunction "20_20") (pintype "unspecified"))
      (node (ref "H5R") (pin "20") (pinfunction "20_20") (pintype "unspecified"))
      (node (ref "U1") (pin "15") (pinfunction "PC0_15") (pintype "unspecified"))
      (node (ref "U2") (pin "25") (pinfunction "A0_25") (pintype "unspecified"))
      (node (ref "U3") (pin "25") (pinfunction "A0_25") (pintype "unspecified"))
    )
    (net (code "55") (name "SOCKET_A1") (class "Default")
      (node (ref "H1L") (pin "8") (pinfunction "8_8") (pintype "unspecified"))
      (node (ref "H4R") (pin "19") (pinfunction "19_19") (pintype "unspecified"))
      (node (ref "H5R") (pin "19") (pinfunction "19_19") (pintype "unspecified"))
      (node (ref "U1") (pin "16") (pinfunction "PC1_16") (pintype "unspecified"))
      (node (ref "U2") (pin "24") (pinfunction "A1_24") (pintype "unspecified"))
      (node (ref "U3") (pin "24") (pinfunction "A1_24") (pintype "unspecified"))
    )
    (net (code "56") (name "SOCKET_A2") (class "Default")
      (node (ref "H1L") (pin "7") (pinfunction "7_7") (pintype "unspecified"))
      (node (ref "H4R") (pin "18") (pinfunction "18_18") (pintype "unspecified"))
      (node (ref "H5R") (pin "18") (pinfunction "18_18") (pintype "unspecified"))
      (node (ref "U1") (pin "17") (pinfunction "PC2_17") (pintype "unspecified"))
      (node (ref "U2") (pin "23") (pinfunction "A2_23") (pintype "unspecified"))
      (node (ref "U3") (pin "23") (pinfunction "A2_23") (pintype "unspecified"))
    )
    (net (code "57") (name "SOCKET_A3") (class "Default")
      (node (ref "H1L") (pin "6") (pinfunction "6_6") (pintype "unspecified"))
      (node (ref "H4R") (pin "17") (pinfunction "17_17") (pintype "unspecified"))
      (node (ref "H5R") (pin "17") (pinfunction "17_17") (pintype "unspecified"))
      (node (ref "U1") (pin "18") (pinfunction "PC3_18") (pintype "unspecified"))
      (node (ref "U2") (pin "22") (pinfunction "A3_22") (pintype "unspecified"))
      (node (ref "U3") (pin "22") (pinfunction "A3_22") (pintype "unspecified"))
    )
    (net (code "58") (name "SOCKET_A4") (class "Default")
      (node (ref "H1L") (pin "5") (pinfunction "5_5") (pintype "unspecified"))
      (node (ref "H4R") (pin "16") (pinfunction "16_16") (pintype "unspecified"))
      (node (ref "H5R") (pin "16") (pinfunction "16_16") (pintype "unspecified"))
      (node (ref "U1") (pin "33") (pinfunction "PC4_33") (pintype "unspecified"))
      (node (ref "U2") (pin "21") (pinfunction "A4_21") (pintype "unspecified"))
      (node (ref "U3") (pin "21") (pinfunction "A4_21") (pintype "unspecified"))
    )
    (net (code "59") (name "SOCKET_A5") (class "Default")
      (node (ref "H1L") (pin "4") (pinfunction "4_4") (pintype "unspecified"))
      (node (ref "H4R") (pin "15") (pinfunction "15_15") (pintype "unspecified"))
      (node (ref "H5R") (pin "15") (pinfunction "15_15") (pintype "unspecified"))
      (node (ref "U1") (pin "34") (pinfunction "PC5_34") (pintype "unspecified"))
      (node (ref "U2") (pin "20") (pinfunction "A5_20") (pintype "unspecified"))
      (node (ref "U3") (pin "20") (pinfunction "A5_20") (pintype "unspecified"))
    )
    (net (code "60") (name "SOCKET_A6") (class "Default")
      (node (ref "H1L") (pin "3") (pinfunction "3_3") (pintype "unspecified"))
      (node (ref "H4R") (pin "14") (pinfunction "14_14") (pintype "unspecified"))
      (node (ref "H5R") (pin "14") (pinfunction "14_14") (pintype "unspecified"))
      (node (ref "U1") (pin "63") (pinfunction "PC6_63") (pintype "unspecified"))
      (node (ref "U2") (pin "19") (pinfunction "A6_19") (pintype "unspecified"))
      (node (ref "U3") (pin "19") (pinfunction "A6_19") (pintype "unspecified"))
    )
    (net (code "61") (name "SOCKET_A7") (class "Default")
      (node (ref "H1L") (pin "2") (pinfunction "2_2") (pintype "unspecified"))
      (node (ref "H4R") (pin "13") (pinfunction "13_13") (pintype "unspecified"))
      (node (ref "H5R") (pin "13") (pinfunction "13_13") (pintype "unspecified"))
      (node (ref "U1") (pin "64") (pinfunction "PC7_64") (pintype "unspecified"))
      (node (ref "U2") (pin "18") (pinfunction "A7_18") (pintype "unspecified"))
      (node (ref "U3") (pin "18") (pinfunction "A7_18") (pintype "unspecified"))
    )
    (net (code "62") (name "SOCKET_A8") (class "Default")
      (node (ref "H1R") (pin "1") (pinfunction "1_1") (pintype "unspecified"))
      (node (ref "H4R") (pin "12") (pinfunction "12_12") (pintype "unspecified"))
      (node (ref "H5R") (pin "12") (pinfunction "12_12") (pintype "unspecified"))
      (node (ref "U1") (pin "65") (pinfunction "PC8_65") (pintype "unspecified"))
      (node (ref "U2") (pin "8") (pinfunction "A8_8") (pintype "unspecified"))
      (node (ref "U3") (pin "8") (pinfunction "A8_8") (pintype "unspecified"))
    )
    (net (code "63") (name "SOCKET_A9") (class "Default")
      (node (ref "H1R") (pin "2") (pinfunction "2_2") (pintype "unspecified"))
      (node (ref "H4R") (pin "10") (pinfunction "10_10") (pintype "unspecified"))
      (node (ref "H5R") (pin "10") (pinfunction "10_10") (pintype "unspecified"))
      (node (ref "U1") (pin "66") (pinfunction "PC9_66") (pintype "unspecified"))
      (node (ref "U2") (pin "7") (pinfunction "A9_7") (pintype "unspecified"))
      (node (ref "U3") (pin "7") (pinfunction "A9_7") (pintype "unspecified"))
    )
    (net (code "64") (name "SOCKET_A10") (class "Default")
      (node (ref "H1R") (pin "3") (pinfunction "3_3") (pintype "unspecified"))
      (node (ref "H4R") (pin "9") (pinfunction "9_9") (pintype "unspecified"))
      (node (ref "H5R") (pin "9") (pinfunction "9_9") (pintype "unspecified"))
      (node (ref "U1") (pin "78") (pinfunction "PC10_78") (pintype "unspecified"))
      (node (ref "U2") (pin "6") (pinfunction "A10_6") (pintype "unspecified"))
      (node (ref "U3") (pin "6") (pinfunction "A10_6") (pintype "unspecified"))
    )
    (net (code "65") (name "SOCKET_A11") (class "Default")
      (node (ref "H1R") (pin "4") (pinfunction "4_4") (pintype "unspecified"))
      (node (ref "H4R") (pin "8") (pinfunction "8_8") (pintype "unspecified"))
      (node (ref "H5R") (pin "8") (pinfunction "8_8") (pintype "unspecified"))
      (node (ref "U1") (pin "79") (pinfunction "PC11_79") (pintype "unspecified"))
      (node (ref "U2") (pin "5") (pinfunction "A11_5") (pintype "unspecified"))
      (node (ref "U3") (pin "5") (pinfunction "A11_5") (pintype "unspecified"))
    )
    (net (code "66") (name "SOCKET_A12") (class "Default")
      (node (ref "H1R") (pin "5") (pinfunction "5_5") (pintype "unspecified"))
      (node (ref "H4R") (pin "7") (pinfunction "7_7") (pintype "unspecified"))
      (node (ref "H5R") (pin "7") (pinfunction "7_7") (pintype "unspecified"))
      (node (ref "U1") (pin "80") (pinfunction "PC12_80") (pintype "unspecified"))
      (node (ref "U2") (pin "4") (pinfunction "A12_4") (pintype "unspecified"))
      (node (ref "U3") (pin "4") (pinfunction "A12_4") (pintype "unspecified"))
    )
    (net (code "67") (name "SOCKET_A13") (class "Default")
      (node (ref "H1R") (pin "6") (pinfunction "6_6") (pintype "unspecified"))
      (node (ref "H4R") (pin "6") (pinfunction "6_6") (pintype "unspecified"))
      (node (ref "H5R") (pin "6") (pinfunction "6_6") (pintype "unspecified"))
      (node (ref "U1") (pin "24") (pinfunction "PA1_24") (pintype "unspecified"))
      (node (ref "U1") (pin "7") (pinfunction "PC13-TAMPER-RTC_7") (pintype "unspecified"))
      (node (ref "U2") (pin "3") (pinfunction "A13_3") (pintype "unspecified"))
      (node (ref "U3") (pin "3") (pinfunction "A13_3") (pintype "unspecified"))
    )
    (net (code "68") (name "SOCKET_A14") (class "Default")
      (node (ref "H1R") (pin "7") (pinfunction "7_7") (pintype "unspecified"))
      (node (ref "H4R") (pin "5") (pinfunction "5_5") (pintype "unspecified"))
      (node (ref "H5R") (pin "5") (pinfunction "5_5") (pintype "unspecified"))
      (node (ref "U1") (pin "25") (pinfunction "PA2_25") (pintype "unspecified"))
      (node (ref "U1") (pin "8") (pinfunction "PC14-OSC32_IN_8") (pintype "unspecified"))
      (node (ref "U2") (pin "2") (pinfunction "A14_2") (pintype "unspecified"))
      (node (ref "U3") (pin "2") (pinfunction "A14_2") (pintype "unspecified"))
    )
    (net (code "69") (name "SOCKET_A15") (class "Default")
      (node (ref "H1R") (pin "8") (pinfunction "8_8") (pintype "unspecified"))
      (node (ref "H4R") (pin "4") (pinfunction "4_4") (pintype "unspecified"))
      (node (ref "H5R") (pin "4") (pinfunction "4_4") (pintype "unspecified"))
      (node (ref "U1") (pin "26") (pinfunction "PA3_26") (pintype "unspecified"))
      (node (ref "U1") (pin "9") (pinfunction "PC15-OSC32_OUT_9") (pintype "unspecified"))
      (node (ref "U2") (pin "1") (pinfunction "A15_1") (pintype "unspecified"))
      (node (ref "U3") (pin "1") (pinfunction "A15_1") (pintype "unspecified"))
    )
    (net (code "70") (name "SOCKET_A16") (class "Default")
      (node (ref "H1R") (pin "9") (pinfunction "9_9") (pintype "unspecified"))
      (node (ref "H4R") (pin "3") (pinfunction "3_3") (pintype "unspecified"))
      (node (ref "H5R") (pin "3") (pinfunction "3_3") (pintype "unspecified"))
      (node (ref "U1") (pin "29") (pinfunction "PA4_29") (pintype "unspecified"))
      (node (ref "U2") (pin "48") (pinfunction "A16_48") (pintype "unspecified"))
      (node (ref "U3") (pin "48") (pinfunction "A16_48") (pintype "unspecified"))
    )
    (net (code "71") (name "SOCKET_A17") (class "Default")
      (node (ref "H1L") (pin "1") (pinfunction "1_1") (pintype "unspecified"))
      (node (ref "H4R") (pin "2") (pinfunction "2_2") (pintype "unspecified"))
      (node (ref "H9") (pin "1") (pinfunction "1_1") (pintype "input"))
      (node (ref "R16") (pin "2") (pinfunction "2_2") (pintype "input"))
    )
    (net (code "72") (name "SOCKET_A18") (class "Default")
      (node (ref "H7") (pin "1") (pinfunction "1_1") (pintype "unspecified"))
      (node (ref "R9") (pin "2") (pinfunction "2_2") (pintype "input"))
    )
    (net (code "73") (name "SOCKET_A19") (class "Default")
      (node (ref "H8") (pin "1") (pinfunction "1_1") (pintype "unspecified"))
      (node (ref "R8") (pin "2") (pinfunction "2_2") (pintype "input"))
    )
    (net (code "74") (name "SOCKET_D0") (class "Default")
      (node (ref "H1L") (pin "13") (pinfunction "13_13") (pintype "unspecified"))
      (node (ref "H3L") (pin "19") (pinfunction "19_19") (pintype "unspecified"))
      (node (ref "H7L") (pin "19") (pinfunction "19_19") (pintype "unspecified"))
      (node (ref "U5") (pin "23") (pinfunction "4Y4_23") (pintype "unspecified"))
    )
    (net (code "75") (name "SOCKET_D1") (class "Default")
      (node (ref "H1L") (pin "15") (pinfunction "15_15") (pintype "unspecified"))
      (node (ref "H3L") (pin "18") (pinfunction "18_18") (pintype "unspecified"))
      (node (ref "H7L") (pin "18") (pinfunction "18_18") (pintype "unspecified"))
      (node (ref "U5") (pin "22") (pinfunction "4Y3_22") (pintype "unspecified"))
    )
    (net (code "76") (name "SOCKET_D2") (class "Default")
      (node (ref "H1L") (pin "17") (pinfunction "17_17") (pintype "unspecified"))
      (node (ref "H3L") (pin "17") (pinfunction "17_17") (pintype "unspecified"))
      (node (ref "H7L") (pin "17") (pinfunction "17_17") (pintype "unspecified"))
      (node (ref "U5") (pin "20") (pinfunction "4Y2_20") (pintype "unspecified"))
    )
    (net (code "77") (name "SOCKET_D3") (class "Default")
      (node (ref "H1L") (pin "19") (pinfunction "19_19") (pintype "unspecified"))
      (node (ref "H3L") (pin "16") (pinfunction "16_16") (pintype "unspecified"))
      (node (ref "H7L") (pin "16") (pinfunction "16_16") (pintype "unspecified"))
      (node (ref "U5") (pin "19") (pinfunction "4Y1_19") (pintype "unspecified"))
    )
    (net (code "78") (name "SOCKET_D4") (class "Default")
      (node (ref "H1R") (pin "19") (pinfunction "19_19") (pintype "unspecified"))
      (node (ref "H3L") (pin "15") (pinfunction "15_15") (pintype "unspecified"))
      (node (ref "H7L") (pin "15") (pinfunction "15_15") (pintype "unspecified"))
      (node (ref "U5") (pin "17") (pinfunction "3Y4_17") (pintype "unspecified"))
    )
    (net (code "79") (name "SOCKET_D5") (class "Default")
      (node (ref "H1R") (pin "17") (pinfunction "17_17") (pintype "unspecified"))
      (node (ref "H3L") (pin "14") (pinfunction "14_14") (pintype "unspecified"))
      (node (ref "H7L") (pin "14") (pinfunction "14_14") (pintype "unspecified"))
      (node (ref "U5") (pin "16") (pinfunction "3Y3_16") (pintype "unspecified"))
    )
    (net (code "80") (name "SOCKET_D6") (class "Default")
      (node (ref "H1R") (pin "15") (pinfunction "15_15") (pintype "unspecified"))
      (node (ref "H3L") (pin "13") (pinfunction "13_13") (pintype "unspecified"))
      (node (ref "H7L") (pin "13") (pinfunction "13_13") (pintype "unspecified"))
      (node (ref "U5") (pin "14") (pinfunction "3Y2_14") (pintype "unspecified"))
    )
    (net (code "81") (name "SOCKET_D7") (class "Default")
      (node (ref "H1R") (pin "13") (pinfunction "13_13") (pintype "unspecified"))
      (node (ref "H3L") (pin "12") (pinfunction "12_12") (pintype "unspecified"))
      (node (ref "H7L") (pin "12") (pinfunction "12_12") (pintype "unspecified"))
      (node (ref "U5") (pin "13") (pinfunction "3Y1_13") (pintype "unspecified"))
    )
    (net (code "82") (name "SOCKET_D8") (class "Default")
      (node (ref "H1L") (pin "14") (pinfunction "14_14") (pintype "unspecified"))
      (node (ref "H3L") (pin "10") (pinfunction "10_10") (pintype "unspecified"))
      (node (ref "H7L") (pin "10") (pinfunction "10_10") (pintype "unspecified"))
      (node (ref "U5") (pin "12") (pinfunction "2Y4_12") (pintype "unspecified"))
    )
    (net (code "83") (name "SOCKET_D9") (class "Default")
      (node (ref "H1L") (pin "16") (pinfunction "16_16") (pintype "unspecified"))
      (node (ref "H3L") (pin "9") (pinfunction "9_9") (pintype "unspecified"))
      (node (ref "H7L") (pin "9") (pinfunction "9_9") (pintype "unspecified"))
      (node (ref "U5") (pin "11") (pinfunction "2Y3_11") (pintype "unspecified"))
    )
    (net (code "84") (name "SOCKET_D10") (class "Default")
      (node (ref "H1L") (pin "18") (pinfunction "18_18") (pintype "unspecified"))
      (node (ref "H3L") (pin "8") (pinfunction "8_8") (pintype "unspecified"))
      (node (ref "H7L") (pin "8") (pinfunction "8_8") (pintype "unspecified"))
      (node (ref "U5") (pin "9") (pinfunction "2Y2_9") (pintype "unspecified"))
    )
    (net (code "85") (name "SOCKET_D11") (class "Default")
      (node (ref "H1L") (pin "20") (pinfunction "20_20") (pintype "unspecified"))
      (node (ref "H3L") (pin "7") (pinfunction "7_7") (pintype "unspecified"))
      (node (ref "H7L") (pin "7") (pinfunction "7_7") (pintype "unspecified"))
      (node (ref "U5") (pin "8") (pinfunction "2Y1_8") (pintype "unspecified"))
    )
    (net (code "86") (name "SOCKET_D12") (class "Default")
      (node (ref "H1R") (pin "18") (pinfunction "18_18") (pintype "unspecified"))
      (node (ref "H3L") (pin "6") (pinfunction "6_6") (pintype "unspecified"))
      (node (ref "H7L") (pin "6") (pinfunction "6_6") (pintype "unspecified"))
      (node (ref "U5") (pin "6") (pinfunction "1Y4_6") (pintype "unspecified"))
    )
    (net (code "87") (name "SOCKET_D13") (class "Default")
      (node (ref "H1R") (pin "16") (pinfunction "16_16") (pintype "unspecified"))
      (node (ref "H3L") (pin "5") (pinfunction "5_5") (pintype "unspecified"))
      (node (ref "H7L") (pin "5") (pinfunction "5_5") (pintype "unspecified"))
      (node (ref "U5") (pin "5") (pinfunction "1Y3_5") (pintype "unspecified"))
    )
    (net (code "88") (name "SOCKET_D14") (class "Default")
      (node (ref "H1R") (pin "14") (pinfunction "14_14") (pintype "unspecified"))
      (node (ref "H3L") (pin "4") (pinfunction "4_4") (pintype "unspecified"))
      (node (ref "H7L") (pin "4") (pinfunction "4_4") (pintype "unspecified"))
      (node (ref "U5") (pin "3") (pinfunction "1Y2_3") (pintype "unspecified"))
    )
    (net (code "89") (name "SOCKET_D15") (class "Default")
      (node (ref "H1R") (pin "12") (pinfunction "12_12") (pintype "unspecified"))
      (node (ref "H3L") (pin "3") (pinfunction "3_3") (pintype "unspecified"))
      (node (ref "H7L") (pin "3") (pinfunction "3_3") (pintype "unspecified"))
      (node (ref "U5") (pin "2") (pinfunction "1Y1_2") (pintype "unspecified"))
    )
    (net (code "90") (name "SOCKET_D16") (class "Default")
      (node (ref "H2L") (pin "2") (pinfunction "2_2") (pintype "unspecified"))
      (node (ref "H4L") (pin "19") (pinfunction "19_19") (pintype "unspecified"))
      (node (ref "H5L") (pin "19") (pinfunction "19_19") (pintype "unspecified"))
      (node (ref "U6") (pin "23") (pinfunction "4Y4_23") (pintype "unspecified"))
    )
    (net (code "91") (name "SOCKET_D17") (class "Default")
      (node (ref "H2L") (pin "4") (pinfunction "4_4") (pintype "unspecified"))
      (node (ref "H4L") (pin "18") (pinfunction "18_18") (pintype "unspecified"))
      (node (ref "H5L") (pin "18") (pinfunction "18_18") (pintype "unspecified"))
      (node (ref "U6") (pin "22") (pinfunction "4Y3_22") (pintype "unspecified"))
    )
    (net (code "92") (name "SOCKET_D18") (class "Default")
      (node (ref "H2L") (pin "6") (pinfunction "6_6") (pintype "unspecified"))
      (node (ref "H4L") (pin "17") (pinfunction "17_17") (pintype "unspecified"))
      (node (ref "H5L") (pin "17") (pinfunction "17_17") (pintype "unspecified"))
      (node (ref "U6") (pin "20") (pinfunction "4Y2_20") (pintype "unspecified"))
    )
    (net (code "93") (name "SOCKET_D19") (class "Default")
      (node (ref "H2L") (pin "8") (pinfunction "8_8") (pintype "unspecified"))
      (node (ref "H4L") (pin "16") (pinfunction "16_16") (pintype "unspecified"))
      (node (ref "H5L") (pin "16") (pinfunction "16_16") (pintype "unspecified"))
      (node (ref "U6") (pin "19") (pinfunction "4Y1_19") (pintype "unspecified"))
    )
    (net (code "94") (name "SOCKET_D20") (class "Default")
      (node (ref "H2R") (pin "8") (pinfunction "8_8") (pintype "unspecified"))
      (node (ref "H4L") (pin "15") (pinfunction "15_15") (pintype "unspecified"))
      (node (ref "H5L") (pin "15") (pinfunction "15_15") (pintype "unspecified"))
      (node (ref "U6") (pin "17") (pinfunction "3Y4_17") (pintype "unspecified"))
    )
    (net (code "95") (name "SOCKET_D21") (class "Default")
      (node (ref "H2R") (pin "6") (pinfunction "6_6") (pintype "unspecified"))
      (node (ref "H4L") (pin "14") (pinfunction "14_14") (pintype "unspecified"))
      (node (ref "H5L") (pin "14") (pinfunction "14_14") (pintype "unspecified"))
      (node (ref "U6") (pin "16") (pinfunction "3Y3_16") (pintype "unspecified"))
    )
    (net (code "96") (name "SOCKET_D22") (class "Default")
      (node (ref "H2R") (pin "4") (pinfunction "4_4") (pintype "unspecified"))
      (node (ref "H4L") (pin "13") (pinfunction "13_13") (pintype "unspecified"))
      (node (ref "H5L") (pin "13") (pinfunction "13_13") (pintype "unspecified"))
      (node (ref "U6") (pin "14") (pinfunction "3Y2_14") (pintype "unspecified"))
    )
    (net (code "97") (name "SOCKET_D23") (class "Default")
      (node (ref "H2R") (pin "2") (pinfunction "2_2") (pintype "unspecified"))
      (node (ref "H4L") (pin "12") (pinfunction "12_12") (pintype "unspecified"))
      (node (ref "H5L") (pin "12") (pinfunction "12_12") (pintype "unspecified"))
      (node (ref "U6") (pin "13") (pinfunction "3Y1_13") (pintype "unspecified"))
    )
    (net (code "98") (name "SOCKET_D24") (class "Default")
      (node (ref "H2L") (pin "3") (pinfunction "3_3") (pintype "unspecified"))
      (node (ref "H4L") (pin "10") (pinfunction "10_10") (pintype "unspecified"))
      (node (ref "H5L") (pin "10") (pinfunction "10_10") (pintype "unspecified"))
      (node (ref "U6") (pin "12") (pinfunction "2Y4_12") (pintype "unspecified"))
    )
    (net (code "99") (name "SOCKET_D25") (class "Default")
      (node (ref "H2L") (pin "5") (pinfunction "5_5") (pintype "unspecified"))
      (node (ref "H4L") (pin "9") (pinfunction "9_9") (pintype "unspecified"))
      (node (ref "H5L") (pin "9") (pinfunction "9_9") (pintype "unspecified"))
      (node (ref "U6") (pin "11") (pinfunction "2Y3_11") (pintype "unspecified"))
    )
    (net (code "100") (name "SOCKET_D26") (class "Default")
      (node (ref "H2L") (pin "7") (pinfunction "7_7") (pintype "unspecified"))
      (node (ref "H4L") (pin "8") (pinfunction "8_8") (pintype "unspecified"))
      (node (ref "H5L") (pin "8") (pinfunction "8_8") (pintype "unspecified"))
      (node (ref "U6") (pin "9") (pinfunction "2Y2_9") (pintype "unspecified"))
    )
    (net (code "101") (name "SOCKET_D27") (class "Default")
      (node (ref "H2L") (pin "9") (pinfunction "9_9") (pintype "unspecified"))
      (node (ref "H4L") (pin "7") (pinfunction "7_7") (pintype "unspecified"))
      (node (ref "H5L") (pin "7") (pinfunction "7_7") (pintype "unspecified"))
      (node (ref "U6") (pin "8") (pinfunction "2Y1_8") (pintype "unspecified"))
    )
    (net (code "102") (name "SOCKET_D28") (class "Default")
      (node (ref "H2R") (pin "7") (pinfunction "7_7") (pintype "unspecified"))
      (node (ref "H4L") (pin "6") (pinfunction "6_6") (pintype "unspecified"))
      (node (ref "H5L") (pin "6") (pinfunction "6_6") (pintype "unspecified"))
      (node (ref "U6") (pin "6") (pinfunction "1Y4_6") (pintype "unspecified"))
    )
    (net (code "103") (name "SOCKET_D29") (class "Default")
      (node (ref "H2R") (pin "5") (pinfunction "5_5") (pintype "unspecified"))
      (node (ref "H4L") (pin "5") (pinfunction "5_5") (pintype "unspecified"))
      (node (ref "H5L") (pin "5") (pinfunction "5_5") (pintype "unspecified"))
      (node (ref "U6") (pin "5") (pinfunction "1Y3_5") (pintype "unspecified"))
    )
    (net (code "104") (name "SOCKET_D30") (class "Default")
      (node (ref "H2R") (pin "3") (pinfunction "3_3") (pintype "unspecified"))
      (node (ref "H4L") (pin "4") (pinfunction "4_4") (pintype "unspecified"))
      (node (ref "H5L") (pin "4") (pinfunction "4_4") (pintype "unspecified"))
      (node (ref "U6") (pin "3") (pinfunction "1Y2_3") (pintype "unspecified"))
    )
    (net (code "105") (name "SOCKET_D31") (class "Default")
      (node (ref "H2R") (pin "1") (pinfunction "1_1") (pintype "unspecified"))
      (node (ref "H4L") (pin "3") (pinfunction "3_3") (pintype "unspecified"))
      (node (ref "H5L") (pin "3") (pinfunction "3_3") (pintype "unspecified"))
      (node (ref "U1") (pin "51") (pinfunction "PB12_51") (pintype "unspecified"))
      (node (ref "U6") (pin "2") (pinfunction "1Y1_2") (pintype "unspecified"))
    )
    (net (code "106") (name "SOCKET_OE") (class "Default")
      (node (ref "Q1") (pin "1") (pinfunction "G_1") (pintype "unspecified"))
      (node (ref "Q3") (pin "1") (pinfunction "G_1") (pintype "unspecified"))
      (node (ref "R17") (pin "2") (pinfunction "2_2") (pintype "input"))
      (node (ref "R7") (pin "1") (pinfunction "1_1") (pintype "input"))
      (node (ref "U1") (pin "23") (pinfunction "PA0-WKUP_23") (pintype "unspecified"))
      (node (ref "U5") (pin "1") (pinfunction "1OE#_1") (pintype "unspecified"))
      (node (ref "U5") (pin "24") (pinfunction "4OE#_24") (pintype "unspecified"))
      (node (ref "U5") (pin "25") (pinfunction "3OE#_25") (pintype "unspecified"))
      (node (ref "U5") (pin "48") (pinfunction "2OE#_48") (pintype "unspecified"))
      (node (ref "U6") (pin "1") (pinfunction "1OE#_1") (pintype "unspecified"))
      (node (ref "U6") (pin "24") (pinfunction "4OE#_24") (pintype "unspecified"))
      (node (ref "U6") (pin "25") (pinfunction "3OE#_25") (pintype "unspecified"))
      (node (ref "U6") (pin "48") (pinfunction "2OE#_48") (pintype "unspecified"))
    )
    (net (code "107") (name "SOCKET_OE_EXT") (class "Default")
      (node (ref "H1L") (pin "12") (pinfunction "12_12") (pintype "unspecified"))
      (node (ref "H3L") (pin "20") (pinfunction "20_20") (pintype "unspecified"))
      (node (ref "H5L") (pin "20") (pinfunction "20_20") (pintype "unspecified"))
      (node (ref "H7L") (pin "20") (pinfunction "20_20") (pintype "unspecified"))
      (node (ref "R17") (pin "1") (pinfunction "1_1") (pintype "input"))
    )
    (net (code "108") (name "SOCKET_V5") (class "Default")
      (node (ref "D2") (pin "2") (pinfunction "+_2") (pintype "unspecified"))
      (node (ref "H1R") (pin "20") (pinfunction "20_20") (pintype "unspecified"))
      (node (ref "H2R") (pin "9") (pinfunction "9_9") (pintype "unspecified"))
      (node (ref "H4R") (pin "1") (pinfunction "1_1") (pintype "unspecified"))
      (node (ref "H5R") (pin "1") (pinfunction "1_1") (pintype "unspecified"))
      (node (ref "R14") (pin "2") (pinfunction "2_2") (pintype "input"))
    )
    (net (code "109") (name "STM_BOOT0") (class "Default")
      (node (ref "H5") (pin "1") (pinfunction "1_1") (pintype "unspecified"))
      (node (ref "R6") (pin "1") (pinfunction "1_1") (pintype "input"))
      (node (ref "U1") (pin "91") (pinfunction "PB5_91") (pintype "unspecified"))
      (node (ref "U1") (pin "94") (pinfunction "BOOT0_94") (pintype "unspecified"))
    )
    (net (code "110") (name "STM_NRST") (class "Default")
      (node (ref "H6") (pin "5") (pinfunction "5_5") (pintype "input"))
      (node (ref "U1") (pin "14") (pinfunction "NRST_14") (pintype "unspecified"))
    )
    (net (code "111") (name "STM_SWCLK_TCK") (class "Default")
      (node (ref "H6") (pin "2") (pinfunction "2_2") (pintype "input"))
      (node (ref "U1") (pin "76") (pinfunction "PA14_76") (pintype "unspecified"))
    )
    (net (code "112") (name "STM_SWDIO_TMS") (class "Default")
      (node (ref "H6") (pin "4") (pinfunction "4_4") (pintype "input"))
      (node (ref "U1") (pin "72") (pinfunction "PA13_72") (pintype "unspecified"))
    )
    (net (code "113") (name "STM_SWO_TDO") (class "Default")
      (node (ref "H6") (pin "6") (pinfunction "6_6") (pintype "input"))
      (node (ref "U1") (pin "89") (pinfunction "PB3_89") (pintype "unspecified"))
    )
    (net (code "114") (name "USB_CC1") (class "Default")
      (node (ref "R5") (pin "1") (pinfunction "1_1") (pintype "input"))
      (node (ref "U1") (pin "67") (pinfunction "PA8_67") (pintype "unspecified"))
      (node (ref "USBC1") (pin "A5") (pinfunction "CC1_A5") (pintype "unspecified"))
    )
    (net (code "115") (name "USB_CC2") (class "Default")
      (node (ref "R4") (pin "1") (pinfunction "1_1") (pintype "input"))
      (node (ref "U1") (pin "69") (pinfunction "PA10_69") (pintype "unspecified"))
      (node (ref "USBC1") (pin "B5") (pinfunction "CC2_B5") (pintype "unspecified"))
    )
    (net (code "116") (name "USB_DM") (class "Default")
      (node (ref "U1") (pin "70") (pinfunction "PA11_70") (pintype "unspecified"))
      (node (ref "USBC1") (pin "A7") (pinfunction "DN1_A7") (pintype "unspecified"))
      (node (ref "USBC1") (pin "B7") (pinfunction "DN2_B7") (pintype "unspecified"))
    )
    (net (code "117") (name "USB_DP") (class "Default")
      (node (ref "U1") (pin "71") (pinfunction "PA12_71") (pintype "unspecified"))
      (node (ref "USBC1") (pin "A6") (pinfunction "DP1_A6") (pintype "unspecified"))
      (node (ref "USBC1") (pin "B6") (pinfunction "DP2_B6") (pintype "unspecified"))
    )
    (net (code "118") (name "USB_V5") (class "Default")
      (node (ref "D1") (pin "2") (pinfunction "+_2") (pintype "unspecified"))
      (node (ref "U1") (pin "68") (pinfunction "PA9_68") (pintype "unspecified"))
      (node (ref "USBC1") (pin "A4B9") (pinfunction "VBUS_A4B9") (pintype "unspecified"))
      (node (ref "USBC1") (pin "B4A9") (pinfunction "VBUS_B4A9") (pintype "unspecified"))
    )
    (net (code "119") (name "V3P3") (class "Default")
      (node (ref "C4") (pin "1") (pinfunction "1_1") (pintype "input"))
      (node (ref "C5") (pin "2") (pinfunction "2_2") (pintype "unspecified"))
      (node (ref "C6") (pin "1") (pinfunction "1_1") (pintype "input"))
      (node (ref "C7") (pin "1") (pinfunction "1_1") (pintype "input"))
      (node (ref "C8") (pin "1") (pinfunction "1_1") (pintype "input"))
      (node (ref "H6") (pin "1") (pinfunction "1_1") (pintype "input"))
      (node (ref "U1") (pin "100") (pinfunction "VDD_3_100") (pintype "unspecified"))
      (node (ref "U1") (pin "11") (pinfunction "VDD_5_11") (pintype "unspecified"))
      (node (ref "U1") (pin "21") (pinfunction "VREF+_21") (pintype "unspecified"))
      (node (ref "U1") (pin "22") (pinfunction "VDDA_22") (pintype "unspecified"))
      (node (ref "U1") (pin "28") (pinfunction "VDD_4_28") (pintype "unspecified"))
      (node (ref "U1") (pin "50") (pinfunction "VDD_1_50") (pintype "unspecified"))
      (node (ref "U1") (pin "6") (pinfunction "VBAT_6") (pintype "unspecified"))
      (node (ref "U1") (pin "75") (pinfunction "VDD_2_75") (pintype "unspecified"))
      (node (ref "U4") (pin "2") (pinfunction "Vout_2") (pintype "unspecified"))
      (node (ref "U4") (pin "4") (pinfunction "Vout_4") (pintype "unspecified"))
    )
    (net (code "120") (name "V5") (class "Default")
      (node (ref "C1") (pin "1") (pinfunction "1_1") (pintype "input"))
      (node (ref "C2") (pin "1") (pinfunction "1_1") (pintype "input"))
      (node (ref "C3") (pin "2") (pinfunction "2_2") (pintype "unspecified"))
      (node (ref "D1") (pin "1") (pinfunction "-_1") (pintype "unspecified"))
      (node (ref "D2") (pin "1") (pinfunction "-_1") (pintype "unspecified"))
      (node (ref "LED3") (pin "2") (pinfunction "+_2") (pintype "unspecified"))
      (node (ref "Q1") (pin "2") (pinfunction "S_2") (pintype "unspecified"))
      (node (ref "R11") (pin "2") (pinfunction "2_2") (pintype "input"))
      (node (ref "R12") (pin "1") (pinfunction "1_1") (pintype "input"))
      (node (ref "U2") (pin "37") (pinfunction "VCC_37") (pintype "passive"))
      (node (ref "U2") (pin "47") (pinfunction "BYTE_47") (pintype "unspecified"))
      (node (ref "U3") (pin "37") (pinfunction "VCC_37") (pintype "passive"))
      (node (ref "U3") (pin "47") (pinfunction "BYTE_47") (pintype "unspecified"))
      (node (ref "U4") (pin "3") (pinfunction "Vin_3") (pintype "unspecified"))
      (node (ref "U5") (pin "18") (pinfunction "VCC_18") (pintype "unspecified"))
      (node (ref "U5") (pin "31") (pinfunction "VCC_31") (pintype "unspecified"))
      (node (ref "U5") (pin "42") (pinfunction "VCC_42") (pintype "unspecified"))
      (node (ref "U5") (pin "7") (pinfunction "VCC_7") (pintype "unspecified"))
      (node (ref "U6") (pin "18") (pinfunction "VCC_18") (pintype "unspecified"))
      (node (ref "U6") (pin "31") (pinfunction "VCC_31") (pintype "unspecified"))
      (node (ref "U6") (pin "42") (pinfunction "VCC_42") (pintype "unspecified"))
      (node (ref "U6") (pin "7") (pinfunction "VCC_7") (pintype "unspecified"))
    )
    (net (code "121") (name "unconnected-(H1L-Pad10)") (class "Default")
      (node (ref "H1L") (pin "10") (pinfunction "10_10") (pintype "unspecified+no_connect"))
    )
    (net (code "122") (name "unconnected-(H1R-Pad10)") (class "Default")
      (node (ref "H1R") (pin "10") (pinfunction "10_10") (pintype "unspecified+no_connect"))
    )
    (net (code "123") (name "unconnected-(H2L-Pad1)") (class "Default")
      (node (ref "H2L") (pin "1") (pinfunction "1_1") (pintype "unspecified+no_connect"))
    )
    (net (code "124") (name "unconnected-(H3L-Pad1)") (class "Default")
      (node (ref "H3L") (pin "1") (pinfunction "1_1") (pintype "unspecified+no_connect"))
    )
    (net (code "125") (name "unconnected-(H3L-Pad2)") (class "Default")
      (node (ref "H3L") (pin "2") (pinfunction "2_2") (pintype "unspecified+no_connect"))
    )
    (net (code "126") (name "unconnected-(H4L-Pad1)") (class "Default")
      (node (ref "H4L") (pin "1") (pinfunction "1_1") (pintype "unspecified+no_connect"))
    )
    (net (code "127") (name "unconnected-(H4L-Pad2)") (class "Default")
      (node (ref "H4L") (pin "2") (pinfunction "2_2") (pintype "unspecified+no_connect"))
    )
    (net (code "128") (name "unconnected-(H4L-Pad20)") (class "Default")
      (node (ref "H4L") (pin "20") (pinfunction "20_20") (pintype "unspecified+no_connect"))
    )
    (net (code "129") (name "unconnected-(H5L-Pad1)") (class "Default")
      (node (ref "H5L") (pin "1") (pinfunction "1_1") (pintype "unspecified+no_connect"))
    )
    (net (code "130") (name "unconnected-(H5L-Pad2)") (class "Default")
      (node (ref "H5L") (pin "2") (pinfunction "2_2") (pintype "unspecified+no_connect"))
    )
    (net (code "131") (name "unconnected-(H5R-Pad2)") (class "Default")
      (node (ref "H5R") (pin "2") (pinfunction "2_2") (pintype "unspecified+no_connect"))
    )
    (net (code "132") (name "unconnected-(H7L-Pad1)") (class "Default")
      (node (ref "H7L") (pin "1") (pinfunction "1_1") (pintype "unspecified+no_connect"))
    )
    (net (code "133") (name "unconnected-(H7L-Pad2)") (class "Default")
      (node (ref "H7L") (pin "2") (pinfunction "2_2") (pintype "unspecified+no_connect"))
    )
    (net (code "134") (name "unconnected-(U1-NC-Pad73)") (class "Default")
      (node (ref "U1") (pin "73") (pinfunction "NC_73") (pintype "unspecified+no_connect"))
    )
    (net (code "135") (name "unconnected-(U1-PA15-Pad77)") (class "Default")
      (node (ref "U1") (pin "77") (pinfunction "PA15_77") (pintype "unspecified+no_connect"))
    )
    (net (code "136") (name "unconnected-(U1-PB1-Pad36)") (class "Default")
      (node (ref "U1") (pin "36") (pinfunction "PB1_36") (pintype "unspecified+no_connect"))
    )
    (net (code "137") (name "unconnected-(U1-PB15-Pad54)") (class "Default")
      (node (ref "U1") (pin "54") (pinfunction "PB15_54") (pintype "unspecified+no_connect"))
    )
    (net (code "138") (name "unconnected-(U2-NC-Pad10)") (class "Default")
      (node (ref "U2") (pin "10") (pinfunction "NC_10") (pintype "unspecified+no_connect"))
    )
    (net (code "139") (name "unconnected-(U2-NC-Pad13)") (class "Default")
      (node (ref "U2") (pin "13") (pinfunction "NC_13") (pintype "unspecified+no_connect"))
    )
    (net (code "140") (name "unconnected-(U2-NC-Pad14)") (class "Default")
      (node (ref "U2") (pin "14") (pinfunction "NC_14") (pintype "unspecified+no_connect"))
    )
    (net (code "141") (name "unconnected-(U3-NC-Pad10)") (class "Default")
      (node (ref "U3") (pin "10") (pinfunction "NC_10") (pintype "unspecified+no_connect"))
    )
    (net (code "142") (name "unconnected-(U3-NC-Pad13)") (class "Default")
      (node (ref "U3") (pin "13") (pinfunction "NC_13") (pintype "unspecified+no_connect"))
    )
    (net (code "143") (name "unconnected-(U3-NC-Pad14)") (class "Default")
      (node (ref "U3") (pin "14") (pinfunction "NC_14") (pintype "unspecified+no_connect"))
    )
    (net (code "144") (name "unconnected-(USBC1-SBU1-PadA8)") (class "Default")
      (node (ref "USBC1") (pin "A8") (pinfunction "SBU1_A8") (pintype "unspecified+no_connect"))
    )
    (net (code "145") (name "unconnected-(USBC1-SBU2-PadB8)") (class "Default")
      (node (ref "USBC1") (pin "B8") (pinfunction "SBU2_B8") (pintype "unspecified+no_connect"))
    )
  )
)
